# speedometer.net
KiCad netlist of a schematic drawn in EAGLE
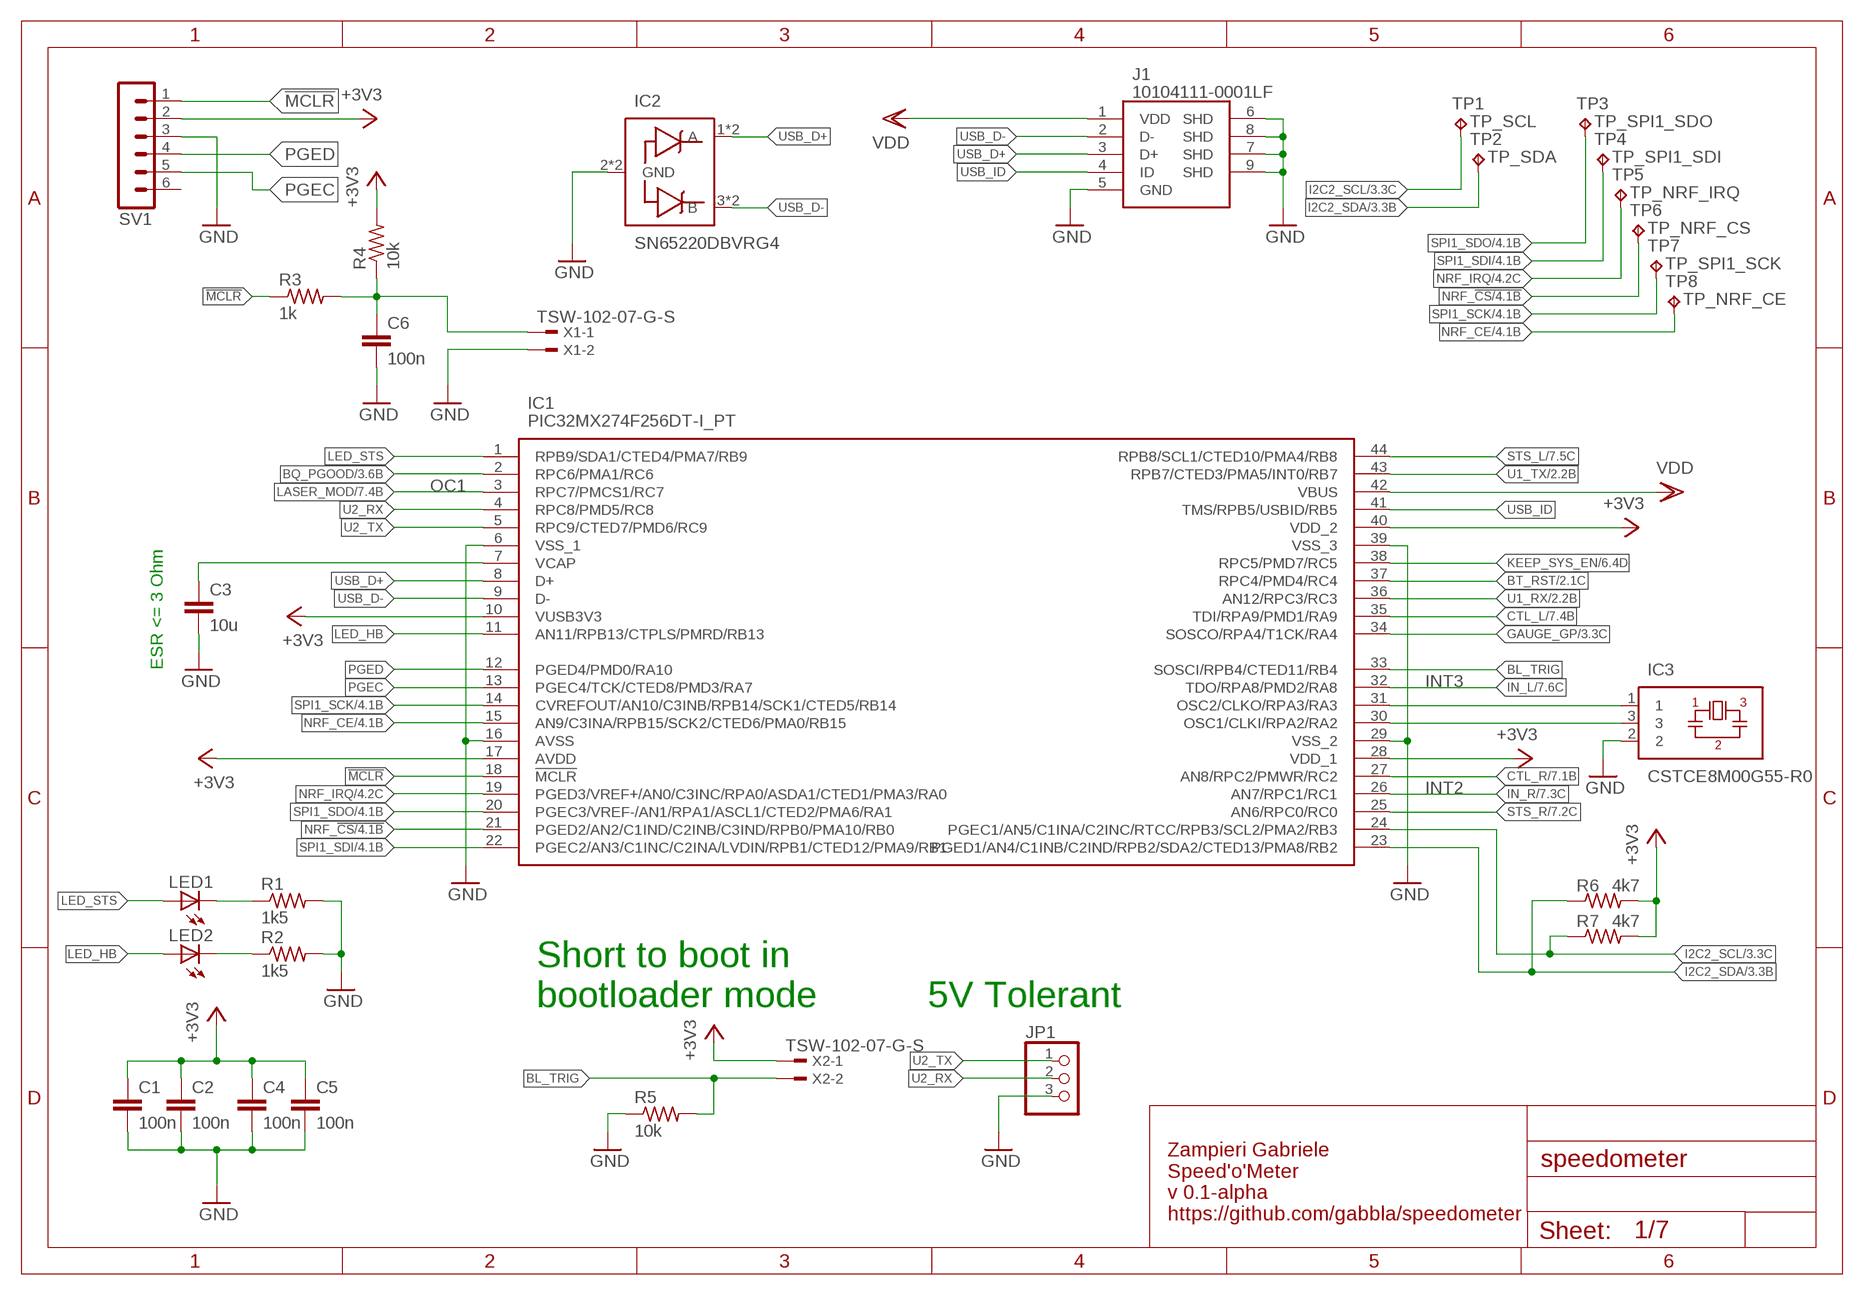
[diagram p0: schematic, sheet 1]
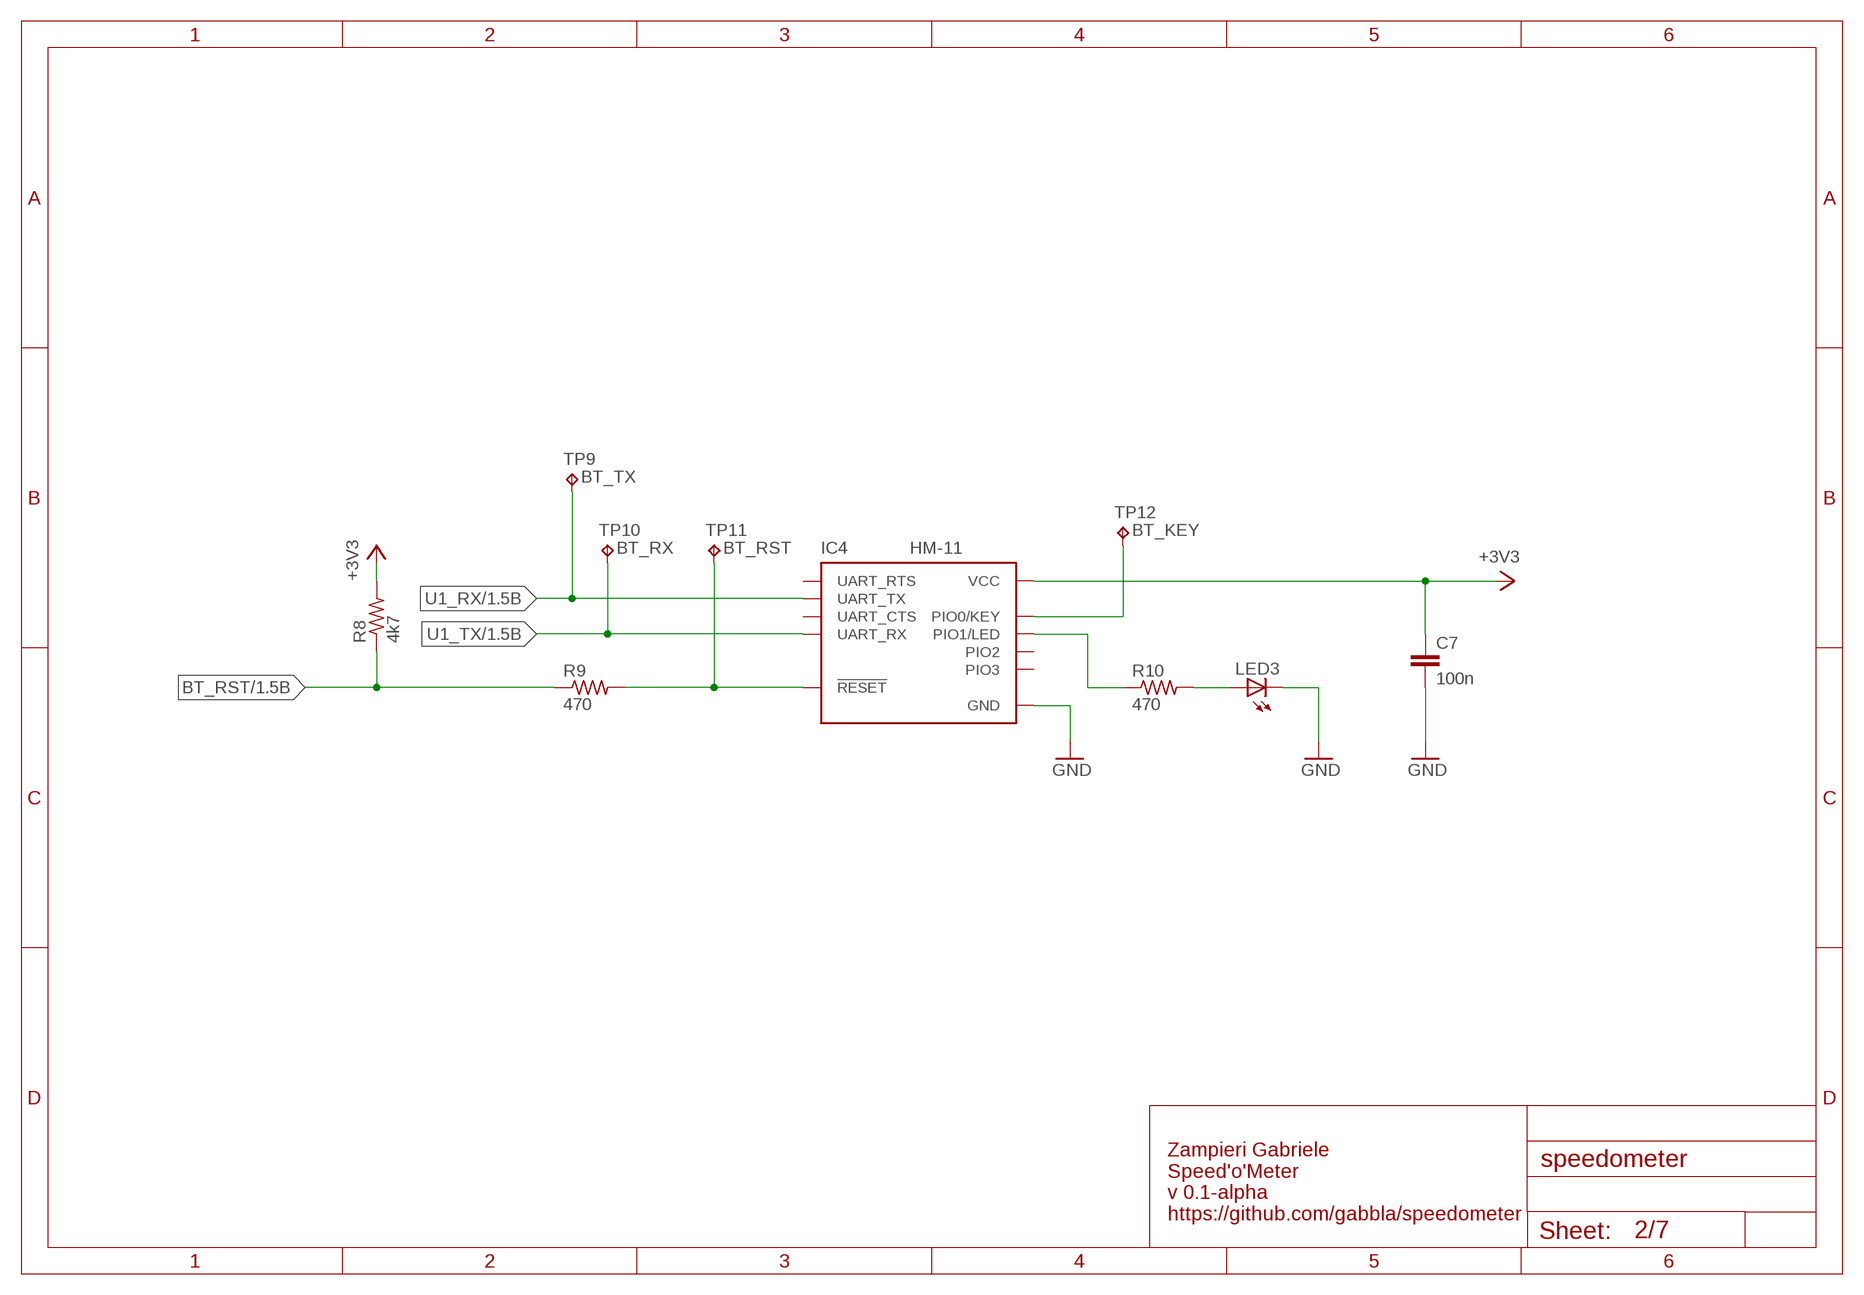
[diagram p1: schematic, sheet 2]
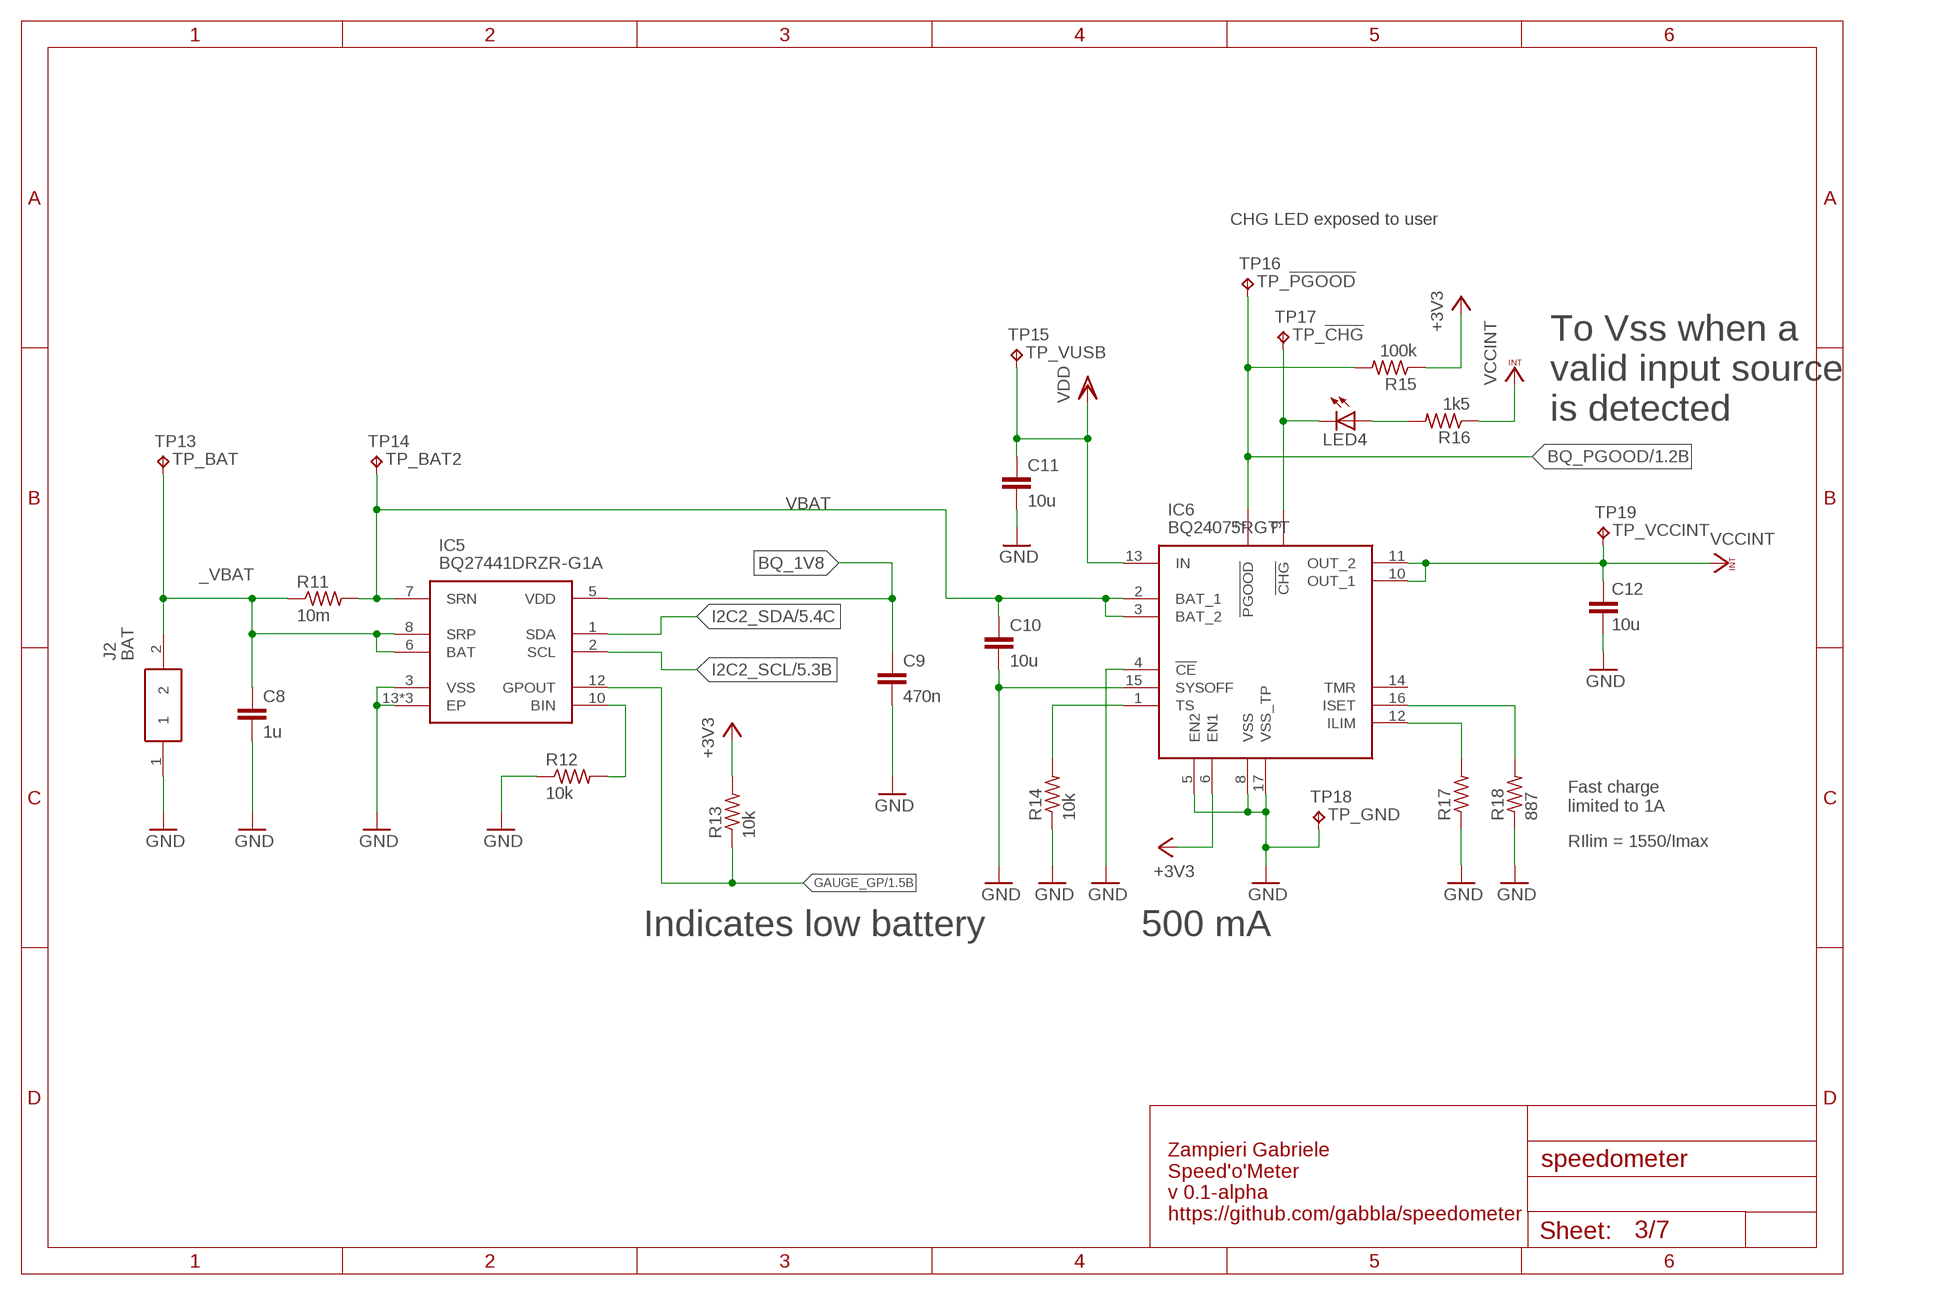
[diagram p2: schematic, sheet 3]
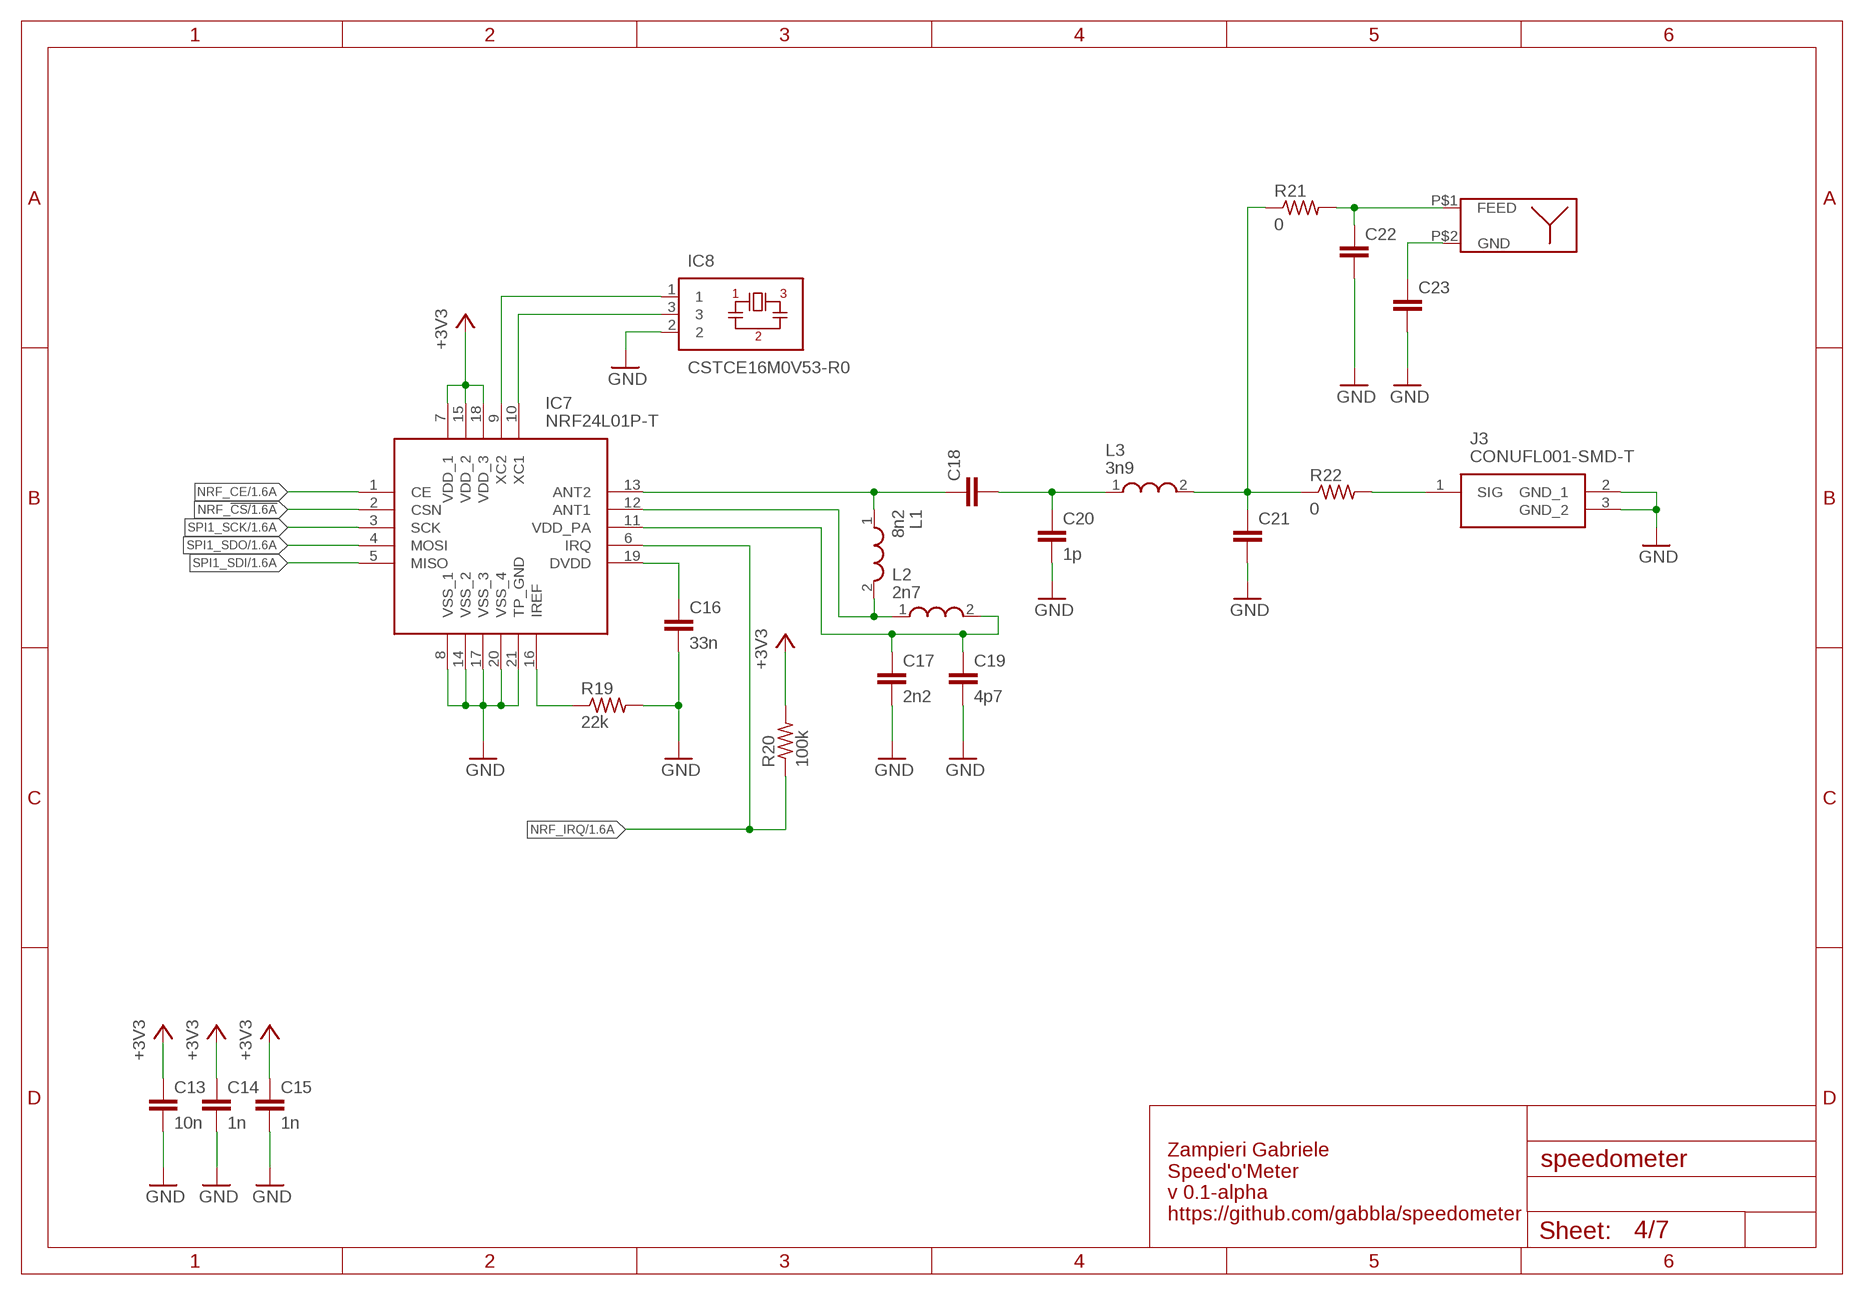
[diagram p3: schematic, sheet 4]
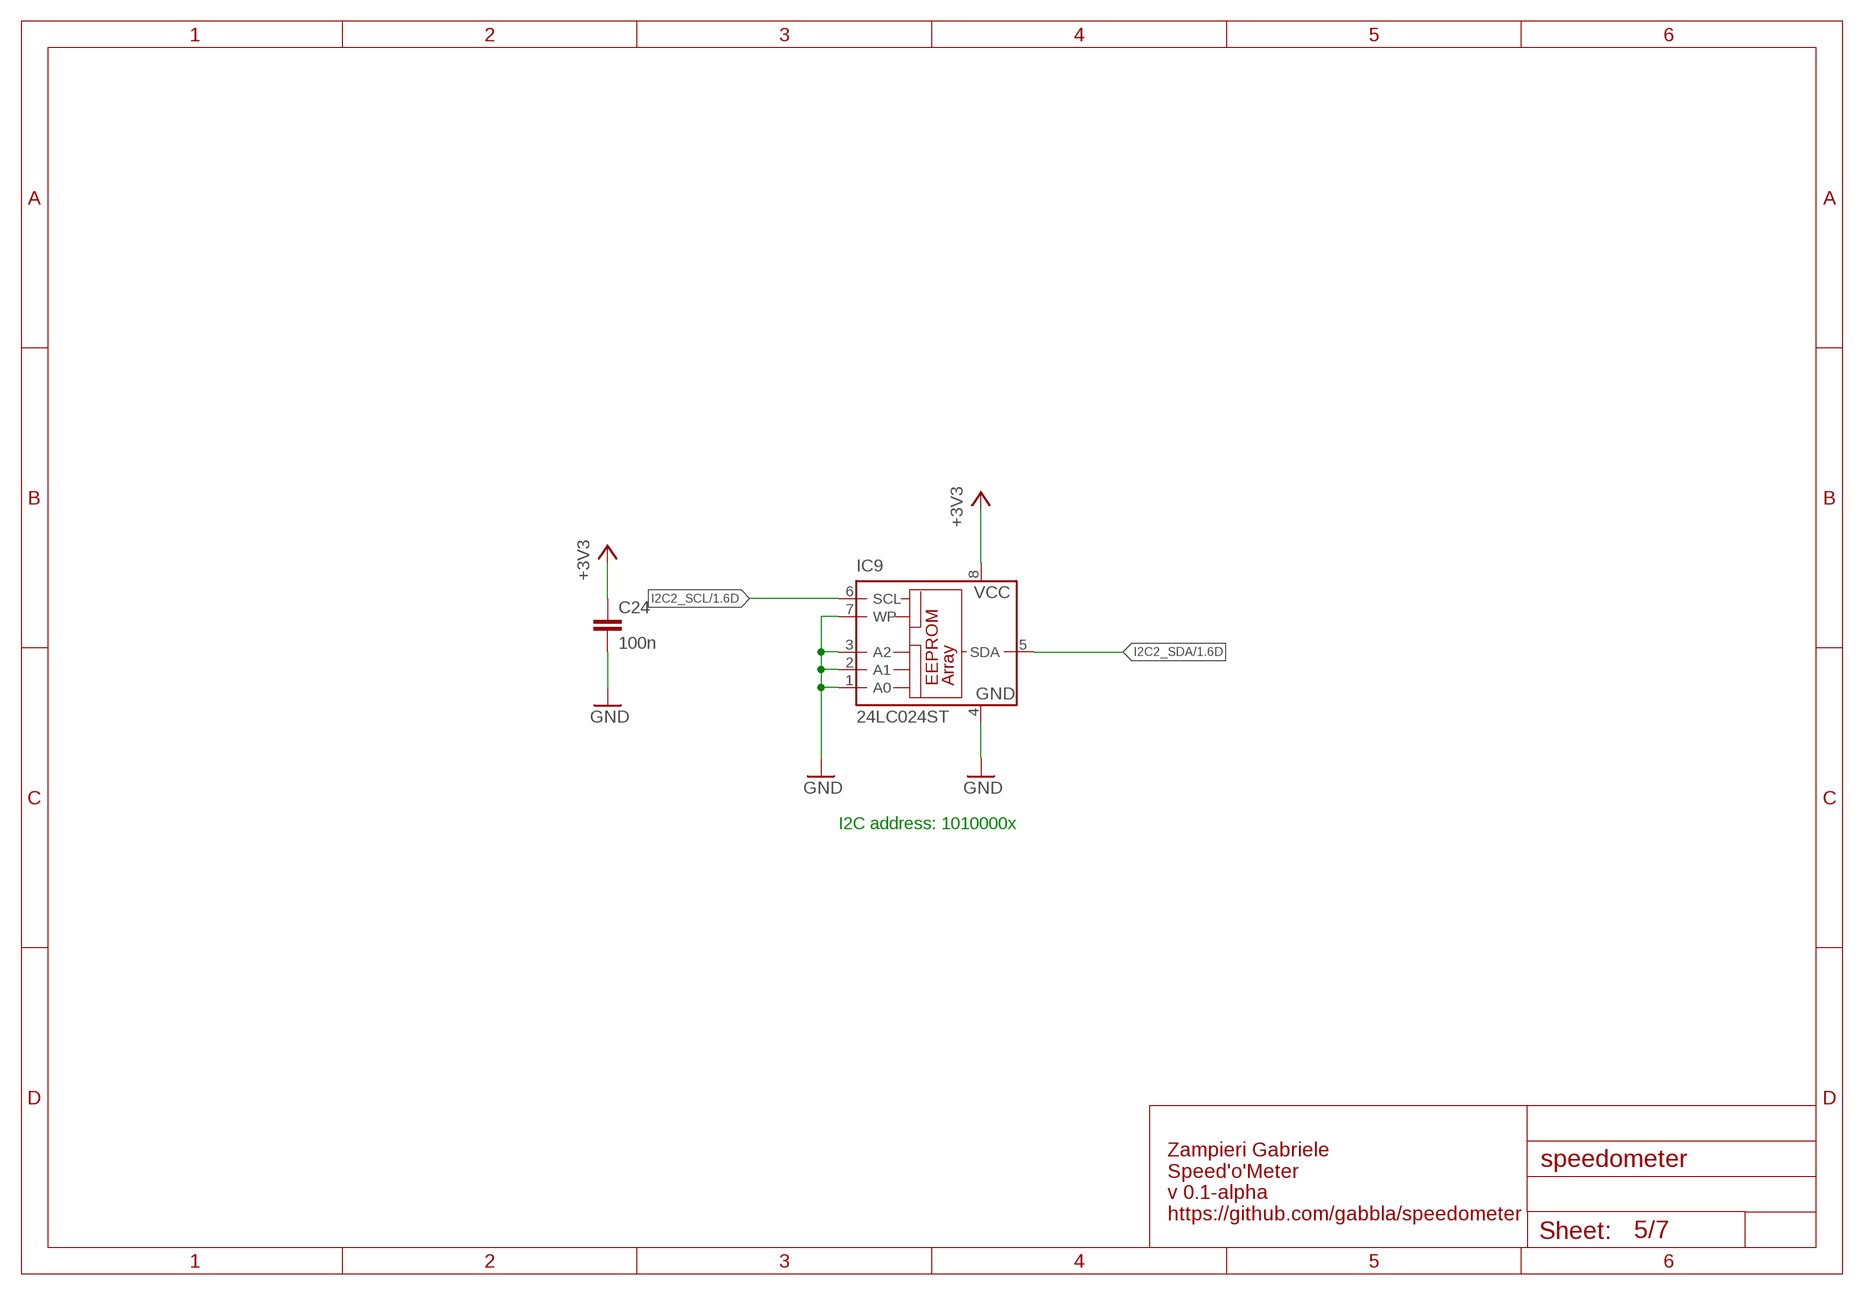
[diagram p4: schematic, sheet 5]
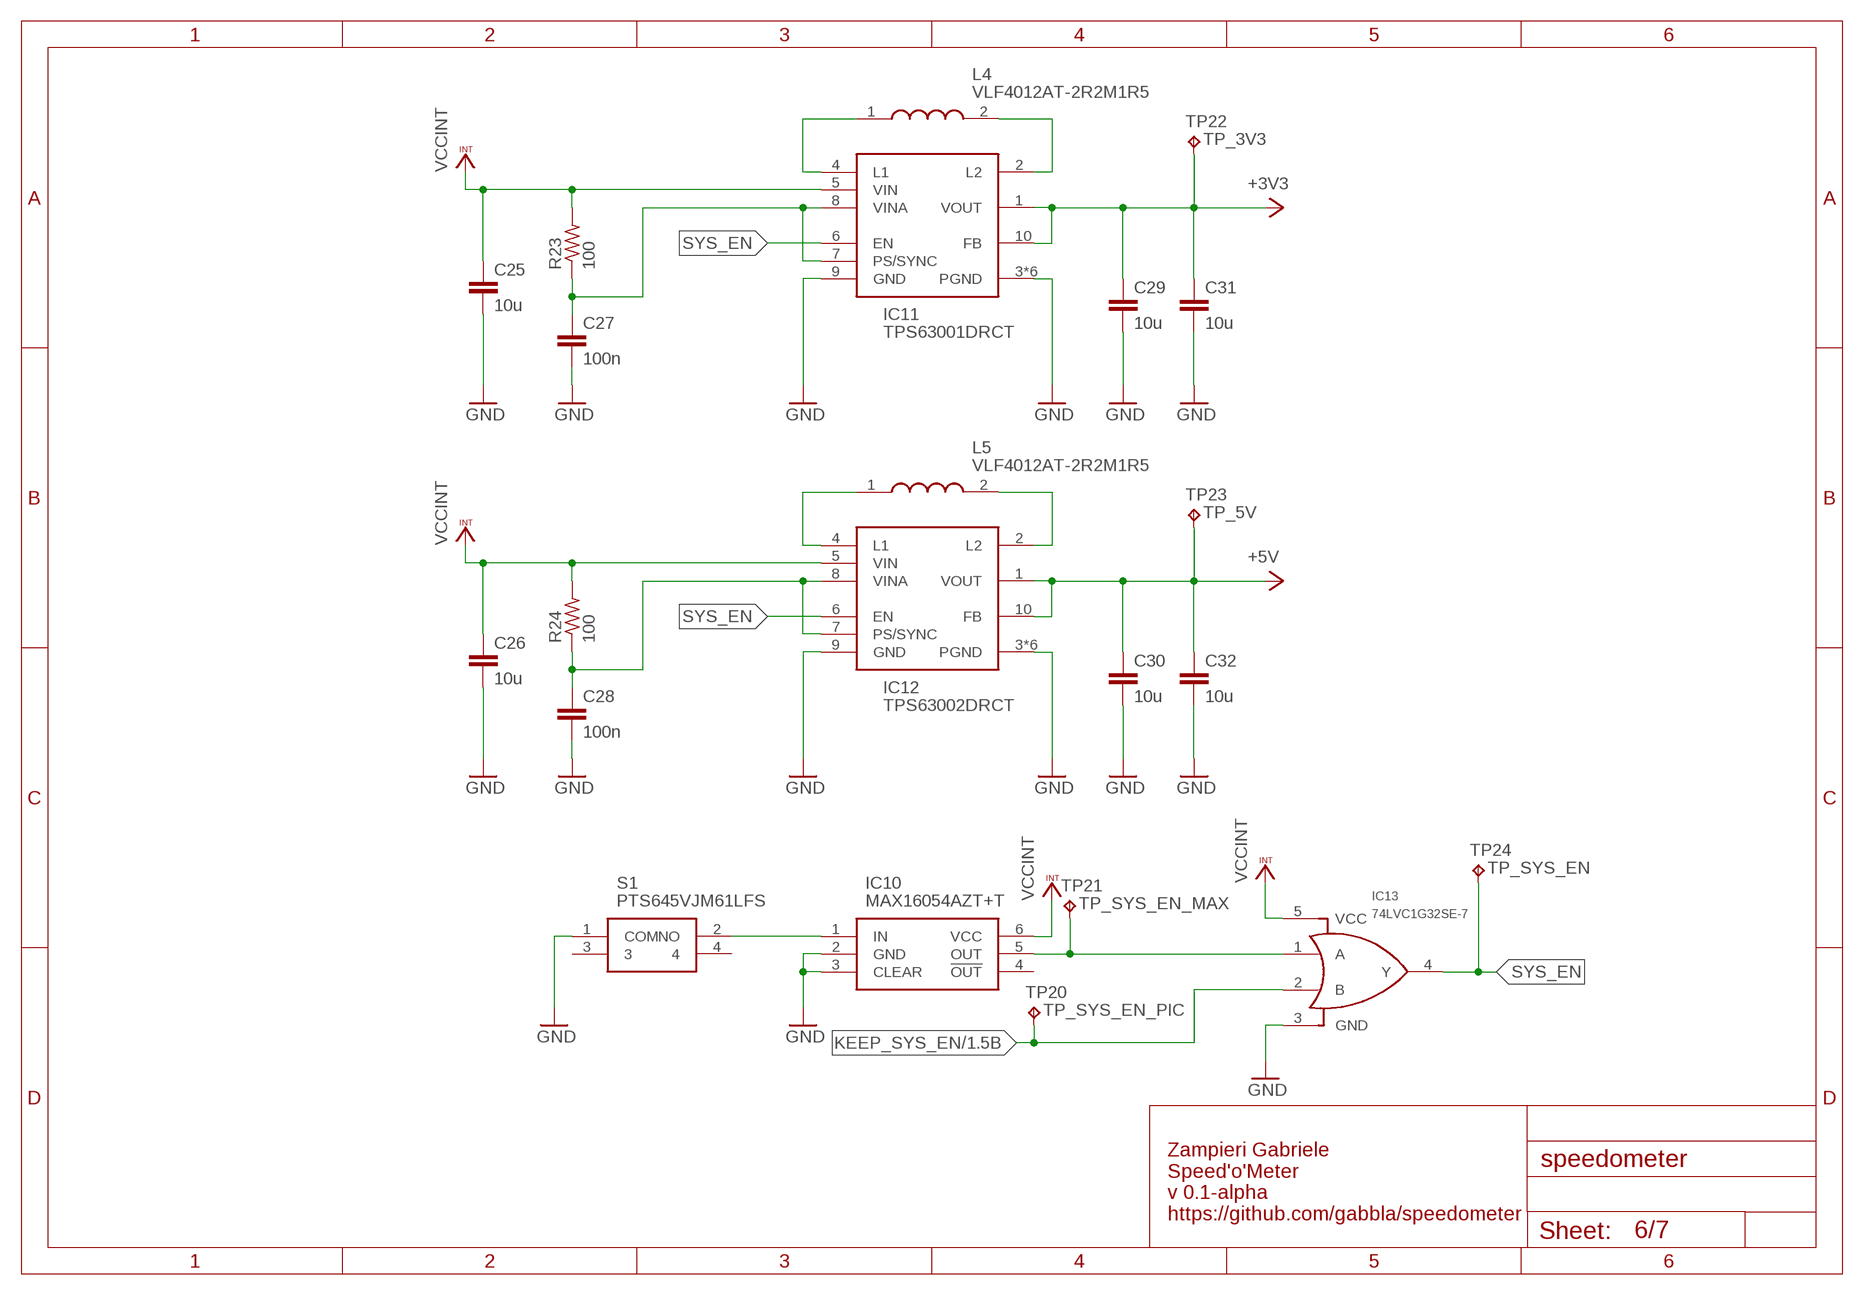
[diagram p5: schematic, sheet 6]
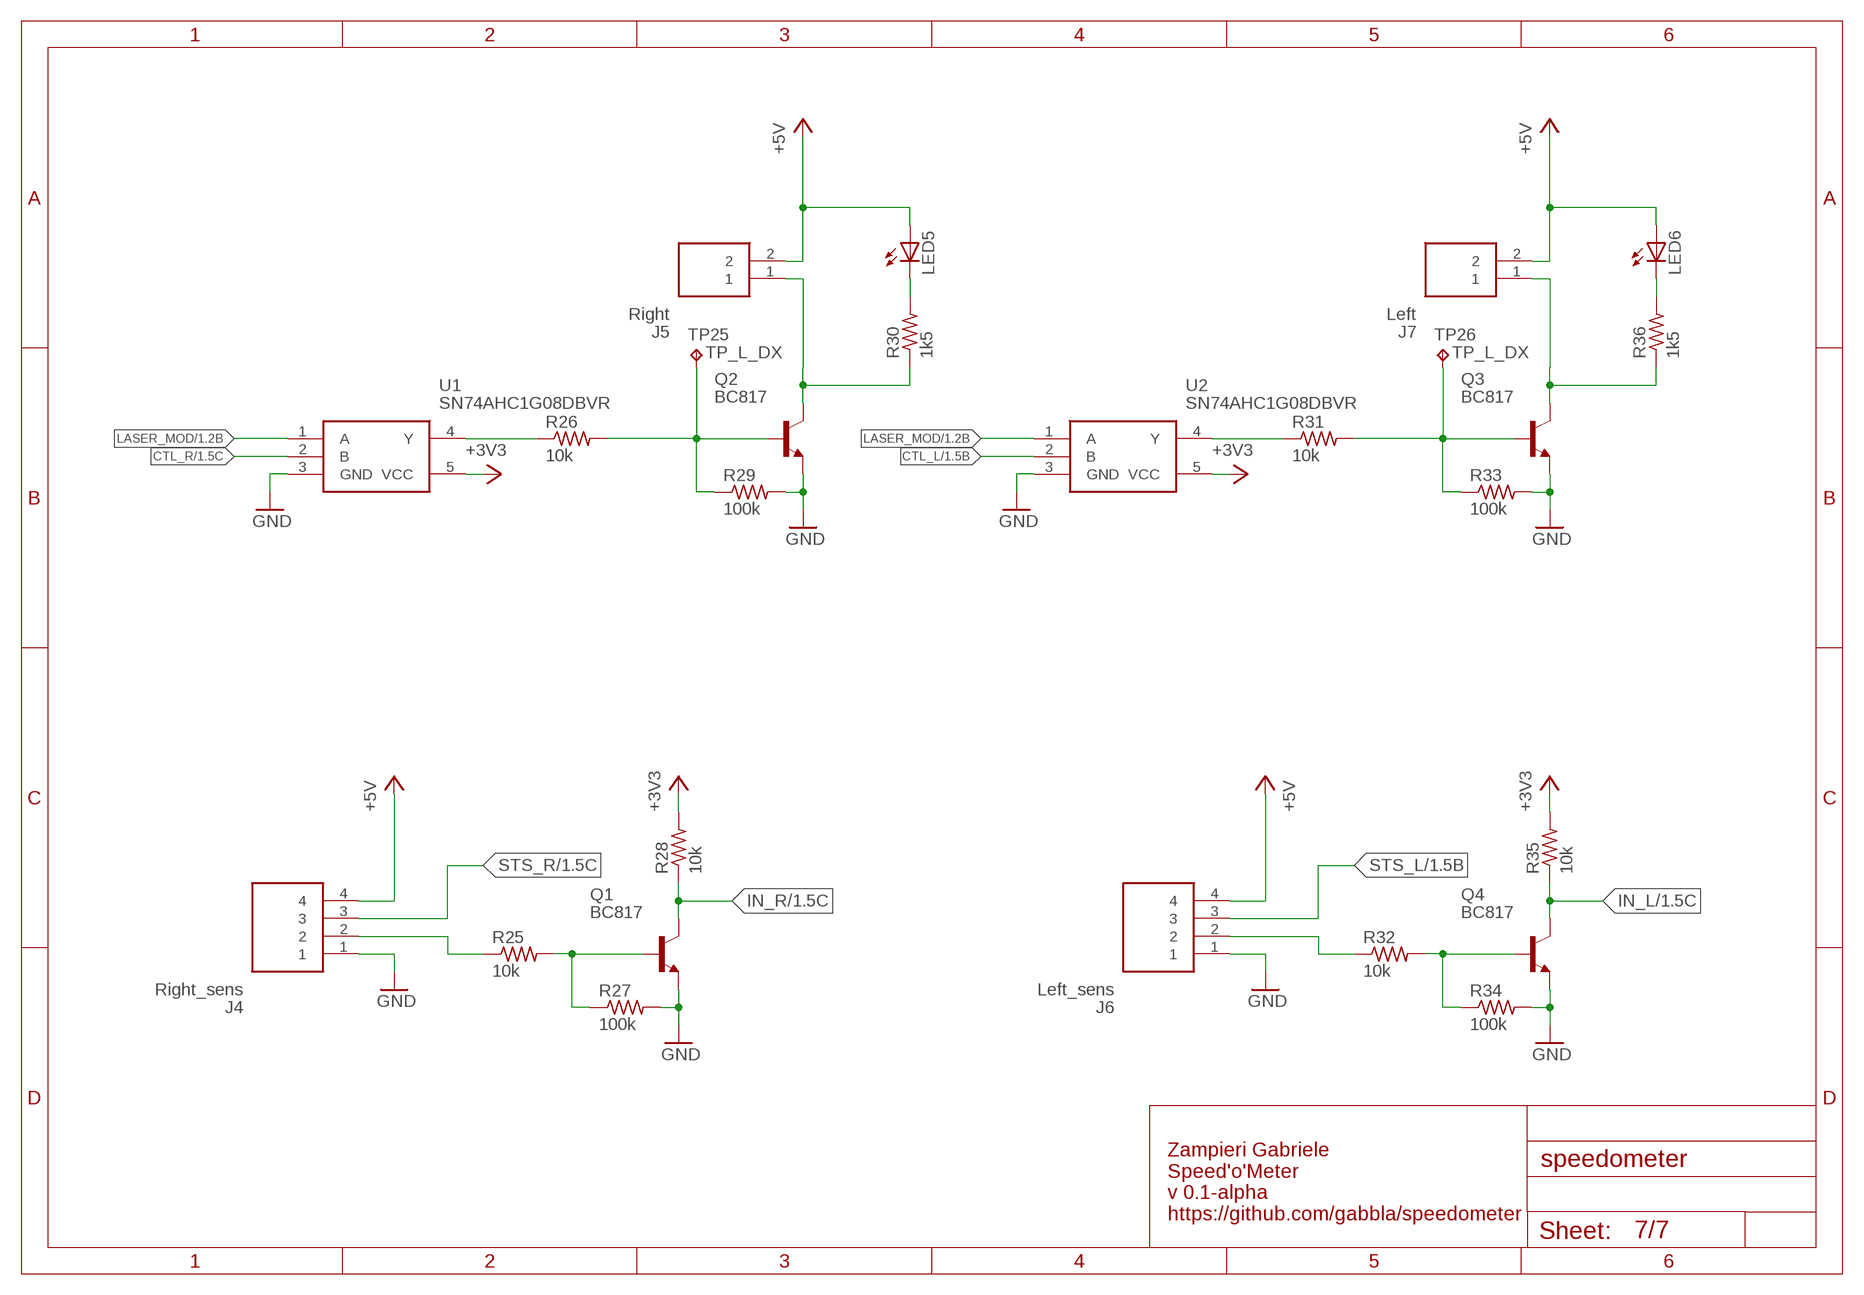
[diagram p6: schematic, sheet 7]

(export (version "E")
  (design (tool "Eeschema 10.0.6"))
  (components
    (comp (ref "C24")
      (value "100n")
      (footprint "eagle-import:C0603K")
      (libsource (lib "eagle-import") (part "C-EUC0603K"))
    )
    (comp (ref "IC9")
      (value "24LC024ST")
      (footprint "eagle-import:TSSOP8")
      (fields (field (name "MPN") "24LC024H-I/ST"))
      (libsource (lib "eagle-import") (part "24STLC024"))
    )
    (comp (ref "C1")
      (value "100n")
      (footprint "eagle-import:C0603K")
      (libsource (lib "eagle-import") (part "C-EUC0603K"))
    )
    (comp (ref "C2")
      (value "100n")
      (footprint "eagle-import:C0603K")
      (libsource (lib "eagle-import") (part "C-EUC0603K"))
    )
    (comp (ref "C3")
      (value "10u")
      (footprint "eagle-import:C0805K")
      (libsource (lib "eagle-import") (part "C-EUC0805K"))
    )
    (comp (ref "C4")
      (value "100n")
      (footprint "eagle-import:C0603K")
      (libsource (lib "eagle-import") (part "C-EUC0603K"))
    )
    (comp (ref "C5")
      (value "100n")
      (footprint "eagle-import:C0603K")
      (libsource (lib "eagle-import") (part "C-EUC0603K"))
    )
    (comp (ref "C6")
      (value "100n")
      (footprint "eagle-import:C0603K")
      (libsource (lib "eagle-import") (part "C-EUC0603K"))
    )
    (comp (ref "IC1")
      (value "PIC32MX274F256DT-I_PT")
      (footprint "eagle-import:QFP80P1200X1200X120-44N")
      (fields (field (name "ARROW_PART_NUMBER") "PIC32MX274F256DT-I/PT"))
      (libsource (lib "eagle-import") (part "PIC32MX274F256DT-I_PT"))
    )
    (comp (ref "IC2")
      (value "SN65220DBVRG4")
      (footprint "eagle-import:SOT95P280X145-6N")
      (libsource (lib "eagle-import") (part "SN65220DBVRG4"))
    )
    (comp (ref "IC3")
      (value "CSTCE8M00G55-R0")
      (footprint "eagle-import:CSTCE_G")
      (fields
        (field (name "ARROW_PART_NUMBER") "CSTCE12M0G15L99-R0")
        (field (name "RS_PART_NUMBER") "7926527P")
      )
      (libsource (lib "eagle-import") (part "CSTCE12M0G15L99-R0"))
    )
    (comp (ref "J1")
      (value "10104111-0001LF")
      (footprint "eagle-import:MICRO_USB_A_B_TYPE_RECEPTACLE")
      (fields (field (name "RS_PART_NUMBER") "1622014"))
      (libsource (lib "eagle-import") (part "10104111-0001LF"))
    )
    (comp (ref "JP1")
      (value "PINHD-1X3")
      (footprint "eagle-import:1X03")
      (libsource (lib "eagle-import") (part "PINHD-1X3"))
    )
    (comp (ref "LED1")
      (value "LED3MM")
      (footprint "eagle-import:LED3MM")
      (libsource (lib "eagle-import") (part "LED3MM"))
    )
    (comp (ref "LED2")
      (value "LEDCHIPLED_0805")
      (footprint "eagle-import:CHIPLED_0805")
      (libsource (lib "eagle-import") (part "LEDCHIPLED_0805"))
    )
    (comp (ref "R1")
      (value "1k5")
      (footprint "eagle-import:R0603")
      (libsource (lib "eagle-import") (part "R-US_R0603"))
    )
    (comp (ref "R2")
      (value "1k5")
      (footprint "eagle-import:R0603")
      (libsource (lib "eagle-import") (part "R-US_R0603"))
    )
    (comp (ref "R3")
      (value "1k")
      (footprint "eagle-import:R0603")
      (libsource (lib "eagle-import") (part "R-US_R0603"))
    )
    (comp (ref "R4")
      (value "10k")
      (footprint "eagle-import:R0603")
      (libsource (lib "eagle-import") (part "R-US_R0603"))
    )
    (comp (ref "R5")
      (value "10k")
      (footprint "eagle-import:R0603")
      (libsource (lib "eagle-import") (part "R-US_R0603"))
    )
    (comp (ref "R6")
      (value "4k7")
      (footprint "eagle-import:R0603")
      (libsource (lib "eagle-import") (part "R-US_R0603"))
    )
    (comp (ref "R7")
      (value "4k7")
      (footprint "eagle-import:R0603")
      (libsource (lib "eagle-import") (part "R-US_R0603"))
    )
    (comp (ref "SV1")
      (value "MA06-1")
      (footprint "eagle-import:MA06-1")
      (libsource (lib "eagle-import") (part "MA06-1"))
    )
    (comp (ref "TP1")
      (value "TPB1,27")
      (footprint "eagle-import:B1,27")
      (fields (field (name "TP_SIGNAL_NAME") "TP_SCL"))
      (libsource (lib "eagle-import") (part "TPB1,27"))
    )
    (comp (ref "TP2")
      (value "TPB1,27")
      (footprint "eagle-import:B1,27")
      (fields (field (name "TP_SIGNAL_NAME") "TP_SDA"))
      (libsource (lib "eagle-import") (part "TPB1,27"))
    )
    (comp (ref "TP3")
      (value "TPB1,27")
      (footprint "eagle-import:B1,27")
      (fields (field (name "TP_SIGNAL_NAME") "TP_SPI1_SDO"))
      (libsource (lib "eagle-import") (part "TPB1,27"))
    )
    (comp (ref "TP4")
      (value "TPB1,27")
      (footprint "eagle-import:B1,27")
      (fields (field (name "TP_SIGNAL_NAME") "TP_SPI1_SDI"))
      (libsource (lib "eagle-import") (part "TPB1,27"))
    )
    (comp (ref "TP5")
      (value "TPB1,27")
      (footprint "eagle-import:B1,27")
      (fields (field (name "TP_SIGNAL_NAME") "TP_NRF_IRQ"))
      (libsource (lib "eagle-import") (part "TPB1,27"))
    )
    (comp (ref "TP6")
      (value "TPB1,27")
      (footprint "eagle-import:B1,27")
      (fields (field (name "TP_SIGNAL_NAME") "TP_NRF_CS"))
      (libsource (lib "eagle-import") (part "TPB1,27"))
    )
    (comp (ref "TP7")
      (value "TPB1,27")
      (footprint "eagle-import:B1,27")
      (fields (field (name "TP_SIGNAL_NAME") "TP_SPI1_SCK"))
      (libsource (lib "eagle-import") (part "TPB1,27"))
    )
    (comp (ref "TP8")
      (value "TPB1,27")
      (footprint "eagle-import:B1,27")
      (fields (field (name "TP_SIGNAL_NAME") "TP_NRF_CE"))
      (libsource (lib "eagle-import") (part "TPB1,27"))
    )
    (comp (ref "X1")
      (value "TSW-102-07-G-S")
      (footprint "eagle-import:TSW-102-XX-G-S")
      (fields (field (name "MF") "Samtec Inc."))
      (libsource (lib "eagle-import") (part "TSW-102--G-S07"))
    )
    (comp (ref "X2")
      (value "TSW-102-07-G-S")
      (footprint "eagle-import:TSW-102-XX-G-S")
      (fields (field (name "MF") "Samtec Inc."))
      (libsource (lib "eagle-import") (part "TSW-102--G-S07"))
    )
    (comp (ref "C25")
      (value "10u")
      (footprint "eagle-import:C0805K")
      (libsource (lib "eagle-import") (part "C-EUC0805K"))
    )
    (comp (ref "C26")
      (value "10u")
      (footprint "eagle-import:C0805K")
      (libsource (lib "eagle-import") (part "C-EUC0805K"))
    )
    (comp (ref "C27")
      (value "100n")
      (footprint "eagle-import:C0603K")
      (libsource (lib "eagle-import") (part "C-EUC0603K"))
    )
    (comp (ref "C28")
      (value "100n")
      (footprint "eagle-import:C0603K")
      (libsource (lib "eagle-import") (part "C-EUC0603K"))
    )
    (comp (ref "C29")
      (value "10u")
      (footprint "eagle-import:C0805K")
      (libsource (lib "eagle-import") (part "C-EUC0805K"))
    )
    (comp (ref "C30")
      (value "10u")
      (footprint "eagle-import:C0805K")
      (libsource (lib "eagle-import") (part "C-EUC0805K"))
    )
    (comp (ref "C31")
      (value "10u")
      (footprint "eagle-import:C0805K")
      (libsource (lib "eagle-import") (part "C-EUC0805K"))
    )
    (comp (ref "C32")
      (value "10u")
      (footprint "eagle-import:C0805K")
      (libsource (lib "eagle-import") (part "C-EUC0805K"))
    )
    (comp (ref "IC10")
      (value "MAX16054AZT+T")
      (footprint "eagle-import:SOT95P275X110-6N")
      (fields (field (name "RS_PART_NUMBER") "9237416"))
      (libsource (lib "eagle-import") (part "MAX16054AZT+T"))
    )
    (comp (ref "IC11")
      (value "TPS63001DRCT")
      (footprint "eagle-import:SON50P300X300X100-11N")
      (fields (field (name "ARROW_PART_NUMBER") "TPS63000DRCT") (field (name "RS_PART_NUMBER") "0389334P"))
      (libsource (lib "eagle-import") (part "TPS63000DRCT"))
    )
    (comp (ref "IC12")
      (value "TPS63002DRCT")
      (footprint "eagle-import:SON50P300X300X100-11N")
      (fields (field (name "ARROW_PART_NUMBER") "TPS63000DRCT") (field (name "RS_PART_NUMBER") "0389334P"))
      (libsource (lib "eagle-import") (part "TPS63000DRCT"))
    )
    (comp (ref "IC13")
      (value "74LVC1G32SE-7")
      (footprint "eagle-import:SOT353")
      (libsource (lib "eagle-import") (part "74LVC1G32SE-7"))
    )
    (comp (ref "L4")
      (value "VLF4012AT-2R2M1R5")
      (footprint "eagle-import:LPS3015")
      (fields (field (name "ARROW_PART_NUMBER") "LPS3015-222MRB") (field (name "RS_PART_NUMBER") " 644-1952"))
      (libsource (lib "eagle-import") (part "LPS3015-222MRB"))
    )
    (comp (ref "L5")
      (value "VLF4012AT-2R2M1R5")
      (footprint "eagle-import:LPS3015")
      (fields (field (name "ARROW_PART_NUMBER") "LPS3015-222MRB") (field (name "RS_PART_NUMBER") " 644-1952"))
      (libsource (lib "eagle-import") (part "LPS3015-222MRB"))
    )
    (comp (ref "R23")
      (value "100")
      (footprint "eagle-import:R0603")
      (fields (field (name "RS_PART_NUMBER") "740-8978"))
      (libsource (lib "eagle-import") (part "R-US_R0603"))
    )
    (comp (ref "R24")
      (value "100")
      (footprint "eagle-import:R0603")
      (fields (field (name "RS_PART_NUMBER") "740-8978"))
      (libsource (lib "eagle-import") (part "R-US_R0603"))
    )
    (comp (ref "S1")
      (value "PTS645VJM61LFS")
      (footprint "eagle-import:PTS645VJM61LFS")
      (libsource (lib "eagle-import") (part "PTS645VJM61LFS"))
    )
    (comp (ref "TP20")
      (value "TPB1,27")
      (footprint "eagle-import:B1,27")
      (fields (field (name "TP_SIGNAL_NAME") "TP_SYS_EN_PIC"))
      (libsource (lib "eagle-import") (part "TPB1,27"))
    )
    (comp (ref "TP21")
      (value "TPB1,27")
      (footprint "eagle-import:B1,27")
      (fields (field (name "TP_SIGNAL_NAME") "TP_SYS_EN_MAX"))
      (libsource (lib "eagle-import") (part "TPB1,27"))
    )
    (comp (ref "TP22")
      (value "TPB1,27")
      (footprint "eagle-import:B1,27")
      (fields (field (name "TP_SIGNAL_NAME") "TP_3V3"))
      (libsource (lib "eagle-import") (part "TPB1,27"))
    )
    (comp (ref "TP23")
      (value "TPB1,27")
      (footprint "eagle-import:B1,27")
      (fields (field (name "TP_SIGNAL_NAME") "TP_5V"))
      (libsource (lib "eagle-import") (part "TPB1,27"))
    )
    (comp (ref "TP24")
      (value "TPB1,27")
      (footprint "eagle-import:B1,27")
      (fields (field (name "TP_SIGNAL_NAME") "TP_SYS_EN"))
      (libsource (lib "eagle-import") (part "TPB1,27"))
    )
    (comp (ref "C8")
      (value "1u")
      (footprint "eagle-import:C0603K")
      (libsource (lib "eagle-import") (part "C-EUC0603K"))
    )
    (comp (ref "C9")
      (value "470n")
      (footprint "eagle-import:C0603K")
      (libsource (lib "eagle-import") (part "C-EUC0603K"))
    )
    (comp (ref "C10")
      (value "10u")
      (footprint "eagle-import:C0805K")
      (libsource (lib "eagle-import") (part "C-EUC0805K"))
    )
    (comp (ref "C11")
      (value "10u")
      (footprint "eagle-import:C0805K")
      (libsource (lib "eagle-import") (part "C-EUC0805K"))
    )
    (comp (ref "C12")
      (value "10u")
      (footprint "eagle-import:C0805K")
      (libsource (lib "eagle-import") (part "C-EUC0805K"))
    )
    (comp (ref "IC5")
      (value "BQ27441DRZR-G1A")
      (footprint "eagle-import:BQ27441DRZRG1A")
      (libsource (lib "eagle-import") (part "BQ27441DRZR-G1A"))
    )
    (comp (ref "IC6")
      (value "BQ24075RGTT")
      (footprint "eagle-import:QFN50P300X300X80-17N")
      (fields (field (name "RS_PART_NUMBER") "8175815P"))
      (libsource (lib "eagle-import") (part "BQ24075RGTT"))
    )
    (comp (ref "J2")
      (value "BAT")
      (footprint "eagle-import:B2B-PH-SM4-TB")
      (fields
        (field (name "MANUFACTURER_PART_NUMBER") "B2B-PH-SM4-TB(LF)(SN)")
        (field (name "RS_PART_NUMBER") "6881325P")
      )
      (libsource (lib "eagle-import") (part "B2B-PH-SM4-TB(LF)(SN)"))
    )
    (comp (ref "LED4")
      (value "LED3MM")
      (footprint "eagle-import:LED3MM")
      (libsource (lib "eagle-import") (part "LED3MM"))
    )
    (comp (ref "R11")
      (value "10m")
      (footprint "eagle-import:R2512")
      (libsource (lib "eagle-import") (part "R-US_R2512"))
    )
    (comp (ref "R12")
      (value "10k")
      (footprint "eagle-import:R0603")
      (libsource (lib "eagle-import") (part "R-US_R0603"))
    )
    (comp (ref "R13")
      (value "10k")
      (footprint "eagle-import:R0603")
      (libsource (lib "eagle-import") (part "R-US_R0603"))
    )
    (comp (ref "R14")
      (value "10k")
      (footprint "eagle-import:R0603")
      (libsource (lib "eagle-import") (part "R-US_R0603"))
    )
    (comp (ref "R15")
      (value "100k")
      (footprint "eagle-import:R0603")
      (libsource (lib "eagle-import") (part "R-US_R0603"))
    )
    (comp (ref "R16")
      (value "1k5")
      (footprint "eagle-import:R0603")
      (libsource (lib "eagle-import") (part "R-US_R0603"))
    )
    (comp (ref "R17")
      (value "R-US_R0603")
      (footprint "eagle-import:R0603")
      (libsource (lib "eagle-import") (part "R-US_R0603"))
    )
    (comp (ref "R18")
      (value "887")
      (footprint "eagle-import:R0603")
      (libsource (lib "eagle-import") (part "R-US_R0603"))
    )
    (comp (ref "TP13")
      (value "TPB1,27")
      (footprint "eagle-import:B1,27")
      (fields (field (name "TP_SIGNAL_NAME") "TP_BAT"))
      (libsource (lib "eagle-import") (part "TPB1,27"))
    )
    (comp (ref "TP14")
      (value "TPB1,27")
      (footprint "eagle-import:B1,27")
      (fields (field (name "TP_SIGNAL_NAME") "TP_BAT2"))
      (libsource (lib "eagle-import") (part "TPB1,27"))
    )
    (comp (ref "TP15")
      (value "TPB1,27")
      (footprint "eagle-import:B1,27")
      (fields (field (name "TP_SIGNAL_NAME") "TP_VUSB"))
      (libsource (lib "eagle-import") (part "TPB1,27"))
    )
    (comp (ref "TP16")
      (value "TPB1,27")
      (footprint "eagle-import:B1,27")
      (fields (field (name "TP_SIGNAL_NAME") "TP_!PGOOD"))
      (libsource (lib "eagle-import") (part "TPB1,27"))
    )
    (comp (ref "TP17")
      (value "TPB1,27")
      (footprint "eagle-import:B1,27")
      (fields (field (name "TP_SIGNAL_NAME") "TP_!CHG"))
      (libsource (lib "eagle-import") (part "TPB1,27"))
    )
    (comp (ref "TP18")
      (value "TPB1,27")
      (footprint "eagle-import:B1,27")
      (fields (field (name "TP_SIGNAL_NAME") "TP_GND"))
      (libsource (lib "eagle-import") (part "TPB1,27"))
    )
    (comp (ref "TP19")
      (value "TPB1,27")
      (footprint "eagle-import:B1,27")
      (fields (field (name "TP_SIGNAL_NAME") "TP_VCCINT"))
      (libsource (lib "eagle-import") (part "TPB1,27"))
    )
    (comp (ref "C7")
      (value "100n")
      (footprint "eagle-import:C0603K")
      (libsource (lib "eagle-import") (part "C-EUC0603K"))
    )
    (comp (ref "IC4")
      (value "HM-11")
      (footprint "eagle-import:HM-11")
      (libsource (lib "eagle-import") (part "HM-11"))
    )
    (comp (ref "LED3")
      (value "LED3MM")
      (footprint "eagle-import:LED3MM")
      (libsource (lib "eagle-import") (part "LED3MM"))
    )
    (comp (ref "R8")
      (value "4k7")
      (footprint "eagle-import:R0603")
      (libsource (lib "eagle-import") (part "R-US_R0603"))
    )
    (comp (ref "R9")
      (value "470")
      (footprint "eagle-import:R0603")
      (libsource (lib "eagle-import") (part "R-US_R0603"))
    )
    (comp (ref "R10")
      (value "470")
      (footprint "eagle-import:R0603")
      (libsource (lib "eagle-import") (part "R-US_R0603"))
    )
    (comp (ref "TP9")
      (value "TPB1,27")
      (footprint "eagle-import:B1,27")
      (fields (field (name "TP_SIGNAL_NAME") "BT_TX"))
      (libsource (lib "eagle-import") (part "TPB1,27"))
    )
    (comp (ref "TP10")
      (value "TPB1,27")
      (footprint "eagle-import:B1,27")
      (fields (field (name "TP_SIGNAL_NAME") "BT_RX"))
      (libsource (lib "eagle-import") (part "TPB1,27"))
    )
    (comp (ref "TP11")
      (value "TPB1,27")
      (footprint "eagle-import:B1,27")
      (fields (field (name "TP_SIGNAL_NAME") "BT_RST"))
      (libsource (lib "eagle-import") (part "TPB1,27"))
    )
    (comp (ref "TP12")
      (value "TPB1,27")
      (footprint "eagle-import:B1,27")
      (fields (field (name "TP_SIGNAL_NAME") "BT_KEY"))
      (libsource (lib "eagle-import") (part "TPB1,27"))
    )
    (comp (ref "J4")
      (value "Right_sens")
      (footprint "eagle-import:SHDR4W64P0X250_1X4_1240X575X70")
      (fields (field (name "ARROW_PART_NUMBER") "B4B-XH-A(LF)(SN)") (field (name "RS_PART_NUMBER") "1724913"))
      (libsource (lib "eagle-import") (part "B4B-XH-A(LF)(SN)"))
    )
    (comp (ref "J5")
      (value "Right")
      (footprint "eagle-import:SHDR2W64P0X250_1X2_740X575X700")
      (fields (field (name "ARROW_PART_NUMBER") "B2B-XH-A(LF)(SN)") (field (name "RS_PART_NUMBER") "1667312"))
      (libsource (lib "eagle-import") (part "B2B-XH-A(LF)(SN)"))
    )
    (comp (ref "J6")
      (value "Left_sens")
      (footprint "eagle-import:SHDR4W64P0X250_1X4_1240X575X70")
      (fields
        (field (name "ARROW_PART_NUMBER") "B4B-XH-A(LF)(SN)")
        (field (name "RS_PART_NUMBER") "1724913")
        (field (name "SPICEPREFIX") "E")
      )
      (libsource (lib "eagle-import") (part "B4B-XH-A(LF)(SN)"))
    )
    (comp (ref "J7")
      (value "Left")
      (footprint "eagle-import:SHDR2W64P0X250_1X2_740X575X700")
      (fields (field (name "ARROW_PART_NUMBER") "B2B-XH-A(LF)(SN)") (field (name "RS_PART_NUMBER") "1667312"))
      (libsource (lib "eagle-import") (part "B2B-XH-A(LF)(SN)"))
    )
    (comp (ref "LED5")
      (value "LEDCHIPLED_1206")
      (footprint "eagle-import:CHIPLED_1206")
      (libsource (lib "eagle-import") (part "LEDCHIPLED_1206"))
    )
    (comp (ref "LED6")
      (value "LEDCHIPLED_1206")
      (footprint "eagle-import:CHIPLED_1206")
      (libsource (lib "eagle-import") (part "LEDCHIPLED_1206"))
    )
    (comp (ref "Q1")
      (value "BC817")
      (footprint "eagle-import:SOT23-BEC")
      (libsource (lib "eagle-import") (part "BC817SMD-16LT1"))
    )
    (comp (ref "Q2")
      (value "BC817")
      (footprint "eagle-import:SOT23-BEC")
      (libsource (lib "eagle-import") (part "BC817SMD-16LT1"))
    )
    (comp (ref "Q3")
      (value "BC817")
      (footprint "eagle-import:SOT23-BEC")
      (libsource (lib "eagle-import") (part "BC817SMD-16LT1"))
    )
    (comp (ref "Q4")
      (value "BC817")
      (footprint "eagle-import:SOT23-BEC")
      (fields (field (name "SPICEPREFIX") "Q"))
      (libsource (lib "eagle-import") (part "BC817SMD-16LT1"))
    )
    (comp (ref "R25")
      (value "10k")
      (footprint "eagle-import:R0603")
      (libsource (lib "eagle-import") (part "R-US_R0603"))
    )
    (comp (ref "R26")
      (value "10k")
      (footprint "eagle-import:R0603")
      (libsource (lib "eagle-import") (part "R-US_R0603"))
    )
    (comp (ref "R27")
      (value "100k")
      (footprint "eagle-import:R0603")
      (libsource (lib "eagle-import") (part "R-US_R0603"))
    )
    (comp (ref "R28")
      (value "10k")
      (footprint "eagle-import:R0603")
      (libsource (lib "eagle-import") (part "R-US_R0603"))
    )
    (comp (ref "R29")
      (value "100k")
      (footprint "eagle-import:R0603")
      (libsource (lib "eagle-import") (part "R-US_R0603"))
    )
    (comp (ref "R30")
      (value "1k5")
      (footprint "eagle-import:R0603")
      (libsource (lib "eagle-import") (part "R-US_R0603"))
    )
    (comp (ref "R31")
      (value "10k")
      (footprint "eagle-import:R0603")
      (libsource (lib "eagle-import") (part "R-US_R0603"))
    )
    (comp (ref "R32")
      (value "10k")
      (footprint "eagle-import:R0603")
      (libsource (lib "eagle-import") (part "R-US_R0603"))
    )
    (comp (ref "R33")
      (value "100k")
      (footprint "eagle-import:R0603")
      (libsource (lib "eagle-import") (part "R-US_R0603"))
    )
    (comp (ref "R34")
      (value "100k")
      (footprint "eagle-import:R0603")
      (libsource (lib "eagle-import") (part "R-US_R0603"))
    )
    (comp (ref "R35")
      (value "10k")
      (footprint "eagle-import:R0603")
      (libsource (lib "eagle-import") (part "R-US_R0603"))
    )
    (comp (ref "R36")
      (value "1k5")
      (footprint "eagle-import:R0603")
      (libsource (lib "eagle-import") (part "R-US_R0603"))
    )
    (comp (ref "TP25")
      (value "TPB1,27")
      (footprint "eagle-import:B1,27")
      (fields (field (name "TP_SIGNAL_NAME") "TP_L_DX"))
      (libsource (lib "eagle-import") (part "TPB1,27"))
    )
    (comp (ref "TP26")
      (value "TPB1,27")
      (footprint "eagle-import:B1,27")
      (fields (field (name "TP_SIGNAL_NAME") "TP_L_DX"))
      (libsource (lib "eagle-import") (part "TPB1,27"))
    )
    (comp (ref "U1")
      (value "SN74AHC1G08DBVR")
      (footprint "eagle-import:SOT95P280X145-5N")
      (fields (field (name "RS_PART_NUMBER") "1218343"))
      (libsource (lib "eagle-import") (part "SN74AHC1G08DBVR"))
    )
    (comp (ref "U2")
      (value "SN74AHC1G08DBVR")
      (footprint "eagle-import:SOT95P280X145-5N")
      (fields (field (name "RS_PART_NUMBER") "1218343"))
      (libsource (lib "eagle-import") (part "SN74AHC1G08DBVR"))
    )
    (comp (ref "ANT1")
      (value "M310210")
      (footprint "eagle-import:M310210")
      (libsource (lib "eagle-import") (part "M310210"))
    )
    (comp (ref "C13")
      (value "10n")
      (footprint "eagle-import:C0603K")
      (libsource (lib "eagle-import") (part "C-EUC0603K"))
    )
    (comp (ref "C14")
      (value "1n")
      (footprint "eagle-import:C0603K")
      (libsource (lib "eagle-import") (part "C-EUC0603K"))
    )
    (comp (ref "C15")
      (value "1n")
      (footprint "eagle-import:C0603K")
      (libsource (lib "eagle-import") (part "C-EUC0603K"))
    )
    (comp (ref "C16")
      (value "33n")
      (footprint "eagle-import:C0402K")
      (libsource (lib "eagle-import") (part "C-EUC0402K"))
    )
    (comp (ref "C17")
      (value "2n2")
      (footprint "eagle-import:C0402K")
      (libsource (lib "eagle-import") (part "C-EUC0402K"))
    )
    (comp (ref "C18")
      (value "C-EUC0402K")
      (footprint "eagle-import:C0402K")
      (libsource (lib "eagle-import") (part "C-EUC0402K"))
    )
    (comp (ref "C19")
      (value "4p7")
      (footprint "eagle-import:C0402K")
      (libsource (lib "eagle-import") (part "C-EUC0402K"))
    )
    (comp (ref "C20")
      (value "1p")
      (footprint "eagle-import:C0402K")
      (libsource (lib "eagle-import") (part "C-EUC0402K"))
    )
    (comp (ref "C21")
      (value "C-EUC0402K")
      (footprint "eagle-import:C0402K")
      (libsource (lib "eagle-import") (part "C-EUC0402K"))
    )
    (comp (ref "C22")
      (value "C-EUC0402K")
      (footprint "eagle-import:C0402K")
      (libsource (lib "eagle-import") (part "C-EUC0402K"))
    )
    (comp (ref "C23")
      (value "C-EUC0402K")
      (footprint "eagle-import:C0402K")
      (libsource (lib "eagle-import") (part "C-EUC0402K"))
    )
    (comp (ref "IC7")
      (value "NRF24L01P-T")
      (footprint "eagle-import:QFN50P400X400X95-21N")
      (fields (field (name "ARROW_PART_NUMBER") "nRF24L01P-T") (field (name "RS_PART_NUMBER") "8855748P"))
      (libsource (lib "eagle-import") (part "NRF24L01P-T"))
    )
    (comp (ref "IC8")
      (value "CSTCE16M0V53-R0")
      (footprint "eagle-import:CSTCE_G")
      (fields
        (field (name "ARROW_PART_NUMBER") "CSTCE12M0G15L99-R0")
        (field (name "RS_PART_NUMBER") "7926527P")
      )
      (libsource (lib "eagle-import") (part "CSTCE12M0G15L99-R0"))
    )
    (comp (ref "J3")
      (value "CONUFL001-SMD-T")
      (footprint "eagle-import:CONUFL001-SMD")
      (libsource (lib "eagle-import") (part "CONUFL001-SMD-T"))
    )
    (comp (ref "L1")
      (value "8n2")
      (footprint "eagle-import:C0402K")
      (libsource (lib "eagle-import") (part "INDUCTOR"))
    )
    (comp (ref "L2")
      (value "2n7")
      (footprint "eagle-import:C0402K")
      (libsource (lib "eagle-import") (part "INDUCTOR"))
    )
    (comp (ref "L3")
      (value "3n9")
      (footprint "eagle-import:C0402K")
      (libsource (lib "eagle-import") (part "INDUCTOR"))
    )
    (comp (ref "R19")
      (value "22k")
      (footprint "eagle-import:R0603")
      (libsource (lib "eagle-import") (part "R-US_R0603"))
    )
    (comp (ref "R20")
      (value "100k")
      (footprint "eagle-import:R0603")
      (libsource (lib "eagle-import") (part "R-US_R0603"))
    )
    (comp (ref "R21")
      (value "0")
      (footprint "eagle-import:R0402")
      (libsource (lib "eagle-import") (part "R-US_R0402"))
    )
    (comp (ref "R22")
      (value "0")
      (footprint "eagle-import:R0402")
      (libsource (lib "eagle-import") (part "R-US_R0402"))
    )
  )
  (nets
    (net (code "1") (name "+3V3") (class "Default")
      (node (ref "C1") (pin "1") (pinfunction "1_1") (pintype "passive"))
      (node (ref "C13") (pin "1") (pinfunction "1_1") (pintype "passive"))
      (node (ref "C14") (pin "1") (pinfunction "1_1") (pintype "passive"))
      (node (ref "C15") (pin "1") (pinfunction "1_1") (pintype "passive"))
      (node (ref "C2") (pin "1") (pinfunction "1_1") (pintype "passive"))
      (node (ref "C24") (pin "1") (pinfunction "1_1") (pintype "passive"))
      (node (ref "C29") (pin "1") (pinfunction "1_1") (pintype "passive"))
      (node (ref "C31") (pin "1") (pinfunction "1_1") (pintype "passive"))
      (node (ref "C4") (pin "1") (pinfunction "1_1") (pintype "passive"))
      (node (ref "C5") (pin "1") (pinfunction "1_1") (pintype "passive"))
      (node (ref "C7") (pin "1") (pinfunction "1_1") (pintype "passive"))
      (node (ref "IC1") (pin "10") (pinfunction "VUSB3V3_10") (pintype "bidirectional"))
      (node (ref "IC1") (pin "17") (pinfunction "AVDD_17") (pintype "bidirectional"))
      (node (ref "IC1") (pin "28") (pinfunction "VDD_1_28") (pintype "bidirectional"))
      (node (ref "IC1") (pin "40") (pinfunction "VDD_2_40") (pintype "bidirectional"))
      (node (ref "IC11") (pin "1") (pinfunction "VOUT_1") (pintype "output"))
      (node (ref "IC11") (pin "10") (pinfunction "FB_10") (pintype "bidirectional"))
      (node (ref "IC4") (pin "VCC") (pinfunction "VCC_VCC") (pintype "bidirectional"))
      (node (ref "IC6") (pin "6") (pinfunction "EN1_6") (pintype "bidirectional"))
      (node (ref "IC7") (pin "15") (pinfunction "VDD_2_15") (pintype "bidirectional"))
      (node (ref "IC7") (pin "18") (pinfunction "VDD_3_18") (pintype "bidirectional"))
      (node (ref "IC7") (pin "7") (pinfunction "VDD_1_7") (pintype "bidirectional"))
      (node (ref "IC9") (pin "8") (pinfunction "VCC_8") (pintype "power_in"))
      (node (ref "R13") (pin "2") (pinfunction "2_2") (pintype "passive"))
      (node (ref "R15") (pin "1") (pinfunction "1_1") (pintype "passive"))
      (node (ref "R20") (pin "2") (pinfunction "2_2") (pintype "passive"))
      (node (ref "R28") (pin "2") (pinfunction "2_2") (pintype "passive"))
      (node (ref "R35") (pin "2") (pinfunction "2_2") (pintype "passive"))
      (node (ref "R4") (pin "2") (pinfunction "2_2") (pintype "passive"))
      (node (ref "R6") (pin "2") (pinfunction "2_2") (pintype "passive"))
      (node (ref "R7") (pin "2") (pinfunction "2_2") (pintype "passive"))
      (node (ref "R8") (pin "2") (pinfunction "2_2") (pintype "passive"))
      (node (ref "SV1") (pin "2") (pinfunction "2_2") (pintype "passive"))
      (node (ref "TP22") (pin "TP") (pinfunction "TP_TP") (pintype "input"))
      (node (ref "U1") (pin "5") (pinfunction "VCC_5") (pintype "bidirectional"))
      (node (ref "U2") (pin "5") (pinfunction "VCC_5") (pintype "bidirectional"))
      (node (ref "X2") (pin "1") (pinfunction "1_1") (pintype "passive"))
    )
    (net (code "2") (name "+5V") (class "Default")
      (node (ref "C30") (pin "1") (pinfunction "1_1") (pintype "passive"))
      (node (ref "C32") (pin "1") (pinfunction "1_1") (pintype "passive"))
      (node (ref "IC12") (pin "1") (pinfunction "VOUT_1") (pintype "output"))
      (node (ref "IC12") (pin "10") (pinfunction "FB_10") (pintype "bidirectional"))
      (node (ref "J4") (pin "4") (pinfunction "4_4") (pintype "bidirectional"))
      (node (ref "J5") (pin "2") (pinfunction "2_2") (pintype "bidirectional"))
      (node (ref "J6") (pin "4") (pinfunction "4_4") (pintype "bidirectional"))
      (node (ref "J7") (pin "2") (pinfunction "2_2") (pintype "bidirectional"))
      (node (ref "LED5") (pin "A") (pinfunction "A_A") (pintype "passive"))
      (node (ref "LED6") (pin "A") (pinfunction "A_A") (pintype "passive"))
      (node (ref "TP23") (pin "TP") (pinfunction "TP_TP") (pintype "input"))
    )
    (net (code "3") (name "BL_TRIG") (class "Default")
      (node (ref "IC1") (pin "33") (pinfunction "SOSCI/RPB4/CTED11/RB4_33") (pintype "bidirectional"))
      (node (ref "R5") (pin "2") (pinfunction "2_2") (pintype "passive"))
      (node (ref "X2") (pin "2") (pinfunction "1_2") (pintype "passive"))
    )
    (net (code "4") (name "BQ_1V8") (class "Default")
      (node (ref "C9") (pin "1") (pinfunction "1_1") (pintype "passive"))
      (node (ref "IC5") (pin "5") (pinfunction "VDD_5") (pintype "bidirectional"))
    )
    (net (code "5") (name "BQ_PGOOD") (class "Default")
      (node (ref "IC1") (pin "2") (pinfunction "RPC6/PMA1/RC6_2") (pintype "bidirectional"))
      (node (ref "IC6") (pin "7") (pinfunction "~{PGOOD}_7") (pintype "bidirectional"))
      (node (ref "R15") (pin "2") (pinfunction "2_2") (pintype "passive"))
      (node (ref "TP16") (pin "TP") (pinfunction "TP_TP") (pintype "input"))
    )
    (net (code "6") (name "BT_RST") (class "Default")
      (node (ref "IC1") (pin "37") (pinfunction "RPC4/PMD4/RC4_37") (pintype "bidirectional"))
      (node (ref "R8") (pin "1") (pinfunction "1_1") (pintype "passive"))
      (node (ref "R9") (pin "1") (pinfunction "1_1") (pintype "passive"))
    )
    (net (code "7") (name "CTL_L") (class "Default")
      (node (ref "IC1") (pin "35") (pinfunction "TDI/RPA9/PMD1/RA9_35") (pintype "bidirectional"))
      (node (ref "U2") (pin "2") (pinfunction "B_2") (pintype "bidirectional"))
    )
    (net (code "8") (name "CTL_R") (class "Default")
      (node (ref "IC1") (pin "27") (pinfunction "AN8/RPC2/PMWR/RC2_27") (pintype "bidirectional"))
      (node (ref "U1") (pin "2") (pinfunction "B_2") (pintype "bidirectional"))
    )
    (net (code "9") (name "GAUGE_GP") (class "Default")
      (node (ref "IC1") (pin "34") (pinfunction "SOSCO/RPA4/T1CK/RA4_34") (pintype "bidirectional"))
      (node (ref "IC5") (pin "12") (pinfunction "GPOUT_12") (pintype "bidirectional"))
      (node (ref "R13") (pin "1") (pinfunction "1_1") (pintype "passive"))
    )
    (net (code "10") (name "GND") (class "Default")
      (node (ref "C1") (pin "2") (pinfunction "2_2") (pintype "passive"))
      (node (ref "C10") (pin "2") (pinfunction "2_2") (pintype "passive"))
      (node (ref "C11") (pin "2") (pinfunction "2_2") (pintype "passive"))
      (node (ref "C12") (pin "2") (pinfunction "2_2") (pintype "passive"))
      (node (ref "C13") (pin "2") (pinfunction "2_2") (pintype "passive"))
      (node (ref "C14") (pin "2") (pinfunction "2_2") (pintype "passive"))
      (node (ref "C15") (pin "2") (pinfunction "2_2") (pintype "passive"))
      (node (ref "C16") (pin "2") (pinfunction "2_2") (pintype "passive"))
      (node (ref "C17") (pin "2") (pinfunction "2_2") (pintype "passive"))
      (node (ref "C19") (pin "2") (pinfunction "2_2") (pintype "passive"))
      (node (ref "C2") (pin "2") (pinfunction "2_2") (pintype "passive"))
      (node (ref "C20") (pin "2") (pinfunction "2_2") (pintype "passive"))
      (node (ref "C21") (pin "2") (pinfunction "2_2") (pintype "passive"))
      (node (ref "C22") (pin "2") (pinfunction "2_2") (pintype "passive"))
      (node (ref "C23") (pin "2") (pinfunction "2_2") (pintype "passive"))
      (node (ref "C24") (pin "2") (pinfunction "2_2") (pintype "passive"))
      (node (ref "C25") (pin "2") (pinfunction "2_2") (pintype "passive"))
      (node (ref "C26") (pin "2") (pinfunction "2_2") (pintype "passive"))
      (node (ref "C27") (pin "2") (pinfunction "2_2") (pintype "passive"))
      (node (ref "C28") (pin "2") (pinfunction "2_2") (pintype "passive"))
      (node (ref "C29") (pin "2") (pinfunction "2_2") (pintype "passive"))
      (node (ref "C3") (pin "2") (pinfunction "2_2") (pintype "passive"))
      (node (ref "C30") (pin "2") (pinfunction "2_2") (pintype "passive"))
      (node (ref "C31") (pin "2") (pinfunction "2_2") (pintype "passive"))
      (node (ref "C32") (pin "2") (pinfunction "2_2") (pintype "passive"))
      (node (ref "C4") (pin "2") (pinfunction "2_2") (pintype "passive"))
      (node (ref "C5") (pin "2") (pinfunction "2_2") (pintype "passive"))
      (node (ref "C6") (pin "2") (pinfunction "2_2") (pintype "passive"))
      (node (ref "C7") (pin "2") (pinfunction "2_2") (pintype "passive"))
      (node (ref "C8") (pin "2") (pinfunction "2_2") (pintype "passive"))
      (node (ref "C9") (pin "2") (pinfunction "2_2") (pintype "passive"))
      (node (ref "IC1") (pin "16") (pinfunction "AVSS_16") (pintype "bidirectional"))
      (node (ref "IC1") (pin "29") (pinfunction "VSS_2_29") (pintype "bidirectional"))
      (node (ref "IC1") (pin "39") (pinfunction "VSS_3_39") (pintype "bidirectional"))
      (node (ref "IC1") (pin "6") (pinfunction "VSS_1_6") (pintype "bidirectional"))
      (node (ref "IC10") (pin "2") (pinfunction "GND_2") (pintype "power_in"))
      (node (ref "IC10") (pin "3") (pinfunction "CLEAR_3") (pintype "bidirectional"))
      (node (ref "IC11") (pin "11") (pinfunction "PGND_11") (pintype "power_in"))
      (node (ref "IC11") (pin "3") (pinfunction "PGND_3") (pintype "power_in"))
      (node (ref "IC11") (pin "9") (pinfunction "GND_9") (pintype "power_in"))
      (node (ref "IC11") (pin "EP1") (pinfunction "PGND_EP1") (pintype "power_in"))
      (node (ref "IC11") (pin "EP2") (pinfunction "PGND_EP2") (pintype "power_in"))
      (node (ref "IC11") (pin "EP3") (pinfunction "PGND_EP3") (pintype "power_in"))
      (node (ref "IC11") (pin "EP4") (pinfunction "PGND_EP4") (pintype "power_in"))
      (node (ref "IC12") (pin "11") (pinfunction "PGND_11") (pintype "power_in"))
      (node (ref "IC12") (pin "3") (pinfunction "PGND_3") (pintype "power_in"))
      (node (ref "IC12") (pin "9") (pinfunction "GND_9") (pintype "power_in"))
      (node (ref "IC12") (pin "EP1") (pinfunction "PGND_EP1") (pintype "power_in"))
      (node (ref "IC12") (pin "EP2") (pinfunction "PGND_EP2") (pintype "power_in"))
      (node (ref "IC12") (pin "EP3") (pinfunction "PGND_EP3") (pintype "power_in"))
      (node (ref "IC12") (pin "EP4") (pinfunction "PGND_EP4") (pintype "power_in"))
      (node (ref "IC13") (pin "3") (pinfunction "GND_3") (pintype "bidirectional"))
      (node (ref "IC2") (pin "2") (pinfunction "GND_2") (pintype "power_in"))
      (node (ref "IC2") (pin "5") (pinfunction "GND_5") (pintype "power_in"))
      (node (ref "IC3") (pin "2") (pinfunction "2_2") (pintype "bidirectional"))
      (node (ref "IC4") (pin "GND") (pinfunction "GND_GND") (pintype "bidirectional"))
      (node (ref "IC5") (pin "13") (pinfunction "EP_13") (pintype "bidirectional"))
      (node (ref "IC5") (pin "14") (pinfunction "EP_14") (pintype "bidirectional"))
      (node (ref "IC5") (pin "15") (pinfunction "EP_15") (pintype "bidirectional"))
      (node (ref "IC5") (pin "3") (pinfunction "VSS_3") (pintype "bidirectional"))
      (node (ref "IC6") (pin "15") (pinfunction "SYSOFF_15") (pintype "bidirectional"))
      (node (ref "IC6") (pin "17") (pinfunction "VSS_TP_17") (pintype "power_in"))
      (node (ref "IC6") (pin "4") (pinfunction "~{CE}_4") (pintype "bidirectional"))
      (node (ref "IC6") (pin "5") (pinfunction "EN2_5") (pintype "bidirectional"))
      (node (ref "IC6") (pin "8") (pinfunction "VSS_8") (pintype "power_in"))
      (node (ref "IC7") (pin "14") (pinfunction "VSS_2_14") (pintype "bidirectional"))
      (node (ref "IC7") (pin "17") (pinfunction "VSS_3_17") (pintype "bidirectional"))
      (node (ref "IC7") (pin "20") (pinfunction "VSS_4_20") (pintype "bidirectional"))
      (node (ref "IC7") (pin "21") (pinfunction "TP_GND_21") (pintype "bidirectional"))
      (node (ref "IC7") (pin "8") (pinfunction "VSS_1_8") (pintype "bidirectional"))
      (node (ref "IC8") (pin "2") (pinfunction "2_2") (pintype "bidirectional"))
      (node (ref "IC9") (pin "1") (pinfunction "A0_1") (pintype "input"))
      (node (ref "IC9") (pin "2") (pinfunction "A1_2") (pintype "input"))
      (node (ref "IC9") (pin "3") (pinfunction "A2_3") (pintype "input"))
      (node (ref "IC9") (pin "4") (pinfunction "GND_4") (pintype "power_in"))
      (node (ref "IC9") (pin "7") (pinfunction "WP_7") (pintype "input"))
      (node (ref "J1") (pin "5") (pinfunction "GND_5") (pintype "bidirectional"))
      (node (ref "J1") (pin "6") (pinfunction "SHD_6") (pintype "bidirectional"))
      (node (ref "J1") (pin "7") (pinfunction "SHD_7") (pintype "bidirectional"))
      (node (ref "J1") (pin "8") (pinfunction "SHD_8") (pintype "bidirectional"))
      (node (ref "J1") (pin "9") (pinfunction "SHD_9") (pintype "bidirectional"))
      (node (ref "J2") (pin "1") (pinfunction "1_1") (pintype "bidirectional"))
      (node (ref "J3") (pin "2") (pinfunction "GND_1_2") (pintype "bidirectional"))
      (node (ref "J3") (pin "3") (pinfunction "GND_2_3") (pintype "bidirectional"))
      (node (ref "J4") (pin "1") (pinfunction "1_1") (pintype "bidirectional"))
      (node (ref "J6") (pin "1") (pinfunction "1_1") (pintype "bidirectional"))
      (node (ref "JP1") (pin "3") (pinfunction "3_3") (pintype "passive"))
      (node (ref "LED3") (pin "K") (pinfunction "C_K") (pintype "passive"))
      (node (ref "Q1") (pin "E") (pinfunction "E_E") (pintype "passive"))
      (node (ref "Q2") (pin "E") (pinfunction "E_E") (pintype "passive"))
      (node (ref "Q3") (pin "E") (pinfunction "E_E") (pintype "passive"))
      (node (ref "Q4") (pin "E") (pinfunction "E_E") (pintype "passive"))
      (node (ref "R1") (pin "2") (pinfunction "2_2") (pintype "passive"))
      (node (ref "R12") (pin "1") (pinfunction "1_1") (pintype "passive"))
      (node (ref "R14") (pin "1") (pinfunction "1_1") (pintype "passive"))
      (node (ref "R17") (pin "1") (pinfunction "1_1") (pintype "passive"))
      (node (ref "R18") (pin "1") (pinfunction "1_1") (pintype "passive"))
      (node (ref "R19") (pin "2") (pinfunction "2_2") (pintype "passive"))
      (node (ref "R2") (pin "2") (pinfunction "2_2") (pintype "passive"))
      (node (ref "R27") (pin "2") (pinfunction "2_2") (pintype "passive"))
      (node (ref "R29") (pin "2") (pinfunction "2_2") (pintype "passive"))
      (node (ref "R33") (pin "2") (pinfunction "2_2") (pintype "passive"))
      (node (ref "R34") (pin "2") (pinfunction "2_2") (pintype "passive"))
      (node (ref "R5") (pin "1") (pinfunction "1_1") (pintype "passive"))
      (node (ref "S1") (pin "1") (pinfunction "COM_1") (pintype "bidirectional"))
      (node (ref "SV1") (pin "3") (pinfunction "3_3") (pintype "passive"))
      (node (ref "TP18") (pin "TP") (pinfunction "TP_TP") (pintype "input"))
      (node (ref "U1") (pin "3") (pinfunction "GND_3") (pintype "bidirectional"))
      (node (ref "U2") (pin "3") (pinfunction "GND_3") (pintype "bidirectional"))
      (node (ref "X1") (pin "2") (pinfunction "1_2") (pintype "passive"))
    )
    (net (code "11") (name "I2C2_SCL") (class "Default")
      (node (ref "IC1") (pin "24") (pinfunction "PGEC1/AN5/C1INA/C2INC/RTCC/RPB3/SCL2/PMA2/RB3_24") (pintype "bidirectional"))
      (node (ref "IC5") (pin "2") (pinfunction "SCL_2") (pintype "bidirectional"))
      (node (ref "IC9") (pin "6") (pinfunction "SCL_6") (pintype "input"))
      (node (ref "R7") (pin "1") (pinfunction "1_1") (pintype "passive"))
      (node (ref "TP1") (pin "TP") (pinfunction "TP_TP") (pintype "input"))
    )
    (net (code "12") (name "I2C2_SDA") (class "Default")
      (node (ref "IC1") (pin "23") (pinfunction "PGED1/AN4/C1INB/C2IND/RPB2/SDA2/CTED13/PMA8/RB2_23") (pintype "bidirectional"))
      (node (ref "IC5") (pin "1") (pinfunction "SDA_1") (pintype "bidirectional"))
      (node (ref "IC9") (pin "5") (pinfunction "SDA_5") (pintype "bidirectional"))
      (node (ref "R6") (pin "1") (pinfunction "1_1") (pintype "passive"))
      (node (ref "TP2") (pin "TP") (pinfunction "TP_TP") (pintype "input"))
    )
    (net (code "13") (name "IN_L") (class "Default")
      (node (ref "IC1") (pin "32") (pinfunction "TDO/RPA8/PMD2/RA8_32") (pintype "bidirectional"))
      (node (ref "Q4") (pin "C") (pinfunction "C_C") (pintype "passive"))
      (node (ref "R35") (pin "1") (pinfunction "1_1") (pintype "passive"))
    )
    (net (code "14") (name "IN_R") (class "Default")
      (node (ref "IC1") (pin "26") (pinfunction "AN7/RPC1/RC1_26") (pintype "bidirectional"))
      (node (ref "Q1") (pin "C") (pinfunction "C_C") (pintype "passive"))
      (node (ref "R28") (pin "1") (pinfunction "1_1") (pintype "passive"))
    )
    (net (code "15") (name "KEEP_SYS_EN") (class "Default")
      (node (ref "IC1") (pin "38") (pinfunction "RPC5/PMD7/RC5_38") (pintype "bidirectional"))
      (node (ref "IC13") (pin "2") (pinfunction "B_2") (pintype "bidirectional"))
      (node (ref "TP20") (pin "TP") (pinfunction "TP_TP") (pintype "input"))
    )
    (net (code "16") (name "LASER_MOD") (class "Default")
      (node (ref "IC1") (pin "3") (pinfunction "RPC7/PMCS1/RC7_3") (pintype "bidirectional"))
      (node (ref "U1") (pin "1") (pinfunction "A_1") (pintype "bidirectional"))
      (node (ref "U2") (pin "1") (pinfunction "A_1") (pintype "bidirectional"))
    )
    (net (code "17") (name "LED_HB") (class "Default")
      (node (ref "IC1") (pin "11") (pinfunction "AN11/RPB13/CTPLS/PMRD/RB13_11") (pintype "bidirectional"))
      (node (ref "LED2") (pin "A") (pinfunction "A_A") (pintype "passive"))
    )
    (net (code "18") (name "LED_STS") (class "Default")
      (node (ref "IC1") (pin "1") (pinfunction "RPB9/SDA1/CTED4/PMA7/RB9_1") (pintype "bidirectional"))
      (node (ref "LED1") (pin "A") (pinfunction "A_A") (pintype "passive"))
    )
    (net (code "19") (name "NRF_CE") (class "Default")
      (node (ref "IC1") (pin "15") (pinfunction "AN9/C3INA/RPB15/SCK2/CTED6/PMA0/RB15_15") (pintype "bidirectional"))
      (node (ref "IC7") (pin "1") (pinfunction "CE_1") (pintype "bidirectional"))
      (node (ref "TP8") (pin "TP") (pinfunction "TP_TP") (pintype "input"))
    )
    (net (code "20") (name "NRF_IRQ") (class "Default")
      (node (ref "IC1") (pin "19") (pinfunction "PGED3/VREF+/AN0/C3INC/RPA0/ASDA1/CTED1/PMA3/RA0_19") (pintype "bidirectional"))
      (node (ref "IC7") (pin "6") (pinfunction "IRQ_6") (pintype "bidirectional"))
      (node (ref "R20") (pin "1") (pinfunction "1_1") (pintype "passive"))
      (node (ref "TP5") (pin "TP") (pinfunction "TP_TP") (pintype "input"))
    )
    (net (code "21") (name "NRF_~{CS}") (class "Default")
      (node (ref "IC1") (pin "21") (pinfunction "PGED2/AN2/C1IND/C2INB/C3IND/RPB0/PMA10/RB0_21") (pintype "bidirectional"))
      (node (ref "IC7") (pin "2") (pinfunction "CSN_2") (pintype "bidirectional"))
      (node (ref "TP6") (pin "TP") (pinfunction "TP_TP") (pintype "input"))
    )
    (net (code "22") (name "Net-(ANT1-FEED)") (class "Default")
      (node (ref "ANT1") (pin "P$1") (pinfunction "FEED_P$1") (pintype "bidirectional"))
      (node (ref "C22") (pin "1") (pinfunction "1_1") (pintype "passive"))
      (node (ref "R21") (pin "2") (pinfunction "2_2") (pintype "passive"))
    )
    (net (code "23") (name "Net-(ANT1-GND)") (class "Default")
      (node (ref "ANT1") (pin "P$2") (pinfunction "GND_P$2") (pintype "bidirectional"))
      (node (ref "C23") (pin "1") (pinfunction "1_1") (pintype "passive"))
    )
    (net (code "24") (name "Net-(C6-Pad1)") (class "Default")
      (node (ref "C6") (pin "1") (pinfunction "1_1") (pintype "passive"))
      (node (ref "R3") (pin "2") (pinfunction "2_2") (pintype "passive"))
      (node (ref "R4") (pin "1") (pinfunction "1_1") (pintype "passive"))
      (node (ref "X1") (pin "1") (pinfunction "1_1") (pintype "passive"))
    )
    (net (code "25") (name "Net-(IC1-OSC1{slash}CLKI{slash}RPA2{slash}RA2)") (class "Default")
      (node (ref "IC1") (pin "30") (pinfunction "OSC1/CLKI/RPA2/RA2_30") (pintype "bidirectional"))
      (node (ref "IC3") (pin "3") (pinfunction "3_3") (pintype "bidirectional"))
    )
    (net (code "26") (name "Net-(IC1-OSC2{slash}CLKO{slash}RPA3{slash}RA3)") (class "Default")
      (node (ref "IC1") (pin "31") (pinfunction "OSC2/CLKO/RPA3/RA3_31") (pintype "bidirectional"))
      (node (ref "IC3") (pin "1") (pinfunction "1_1") (pintype "bidirectional"))
    )
    (net (code "27") (name "Net-(IC1-VCAP)") (class "Default")
      (node (ref "C3") (pin "1") (pinfunction "1_1") (pintype "passive"))
      (node (ref "IC1") (pin "7") (pinfunction "VCAP_7") (pintype "bidirectional"))
    )
    (net (code "28") (name "Net-(IC4-PIO0{slash}KEY)") (class "Default")
      (node (ref "IC4") (pin "PIO0") (pinfunction "PIO0/KEY_PIO0") (pintype "bidirectional"))
      (node (ref "TP12") (pin "TP") (pinfunction "TP_TP") (pintype "input"))
    )
    (net (code "29") (name "Net-(IC4-PIO1{slash}LED)") (class "Default")
      (node (ref "IC4") (pin "PIO1") (pinfunction "PIO1/LED_PIO1") (pintype "bidirectional"))
      (node (ref "R10") (pin "1") (pinfunction "1_1") (pintype "passive"))
    )
    (net (code "30") (name "Net-(IC4-~{RESET})") (class "Default")
      (node (ref "IC4") (pin "RESETB") (pinfunction "~{RESET}_RESETB") (pintype "bidirectional"))
      (node (ref "R9") (pin "2") (pinfunction "2_2") (pintype "passive"))
      (node (ref "TP11") (pin "TP") (pinfunction "TP_TP") (pintype "input"))
    )
    (net (code "31") (name "Net-(IC5-BIN)") (class "Default")
      (node (ref "IC5") (pin "10") (pinfunction "BIN_10") (pintype "bidirectional"))
      (node (ref "R12") (pin "2") (pinfunction "2_2") (pintype "passive"))
    )
    (net (code "32") (name "Net-(IC6-ILIM)") (class "Default")
      (node (ref "IC6") (pin "12") (pinfunction "ILIM_12") (pintype "bidirectional"))
      (node (ref "R17") (pin "2") (pinfunction "2_2") (pintype "passive"))
    )
    (net (code "33") (name "Net-(IC6-ISET)") (class "Default")
      (node (ref "IC6") (pin "16") (pinfunction "ISET_16") (pintype "bidirectional"))
      (node (ref "R18") (pin "2") (pinfunction "2_2") (pintype "passive"))
    )
    (net (code "34") (name "Net-(IC6-TS)") (class "Default")
      (node (ref "IC6") (pin "1") (pinfunction "TS_1") (pintype "bidirectional"))
      (node (ref "R14") (pin "2") (pinfunction "2_2") (pintype "passive"))
    )
    (net (code "35") (name "Net-(IC6-~{CHG})") (class "Default")
      (node (ref "IC6") (pin "9") (pinfunction "~{CHG}_9") (pintype "bidirectional"))
      (node (ref "LED4") (pin "K") (pinfunction "C_K") (pintype "passive"))
      (node (ref "TP17") (pin "TP") (pinfunction "TP_TP") (pintype "input"))
    )
    (net (code "36") (name "Net-(IC7-ANT1)") (class "Default")
      (node (ref "IC7") (pin "12") (pinfunction "ANT1_12") (pintype "bidirectional"))
      (node (ref "L1") (pin "2") (pinfunction "P$2_2") (pintype "bidirectional"))
      (node (ref "L2") (pin "1") (pinfunction "P$1_1") (pintype "bidirectional"))
    )
    (net (code "37") (name "Net-(IC7-ANT2)") (class "Default")
      (node (ref "C18") (pin "1") (pinfunction "1_1") (pintype "passive"))
      (node (ref "IC7") (pin "13") (pinfunction "ANT2_13") (pintype "bidirectional"))
      (node (ref "L1") (pin "1") (pinfunction "P$1_1") (pintype "bidirectional"))
    )
    (net (code "38") (name "Net-(IC7-DVDD)") (class "Default")
      (node (ref "C16") (pin "1") (pinfunction "1_1") (pintype "passive"))
      (node (ref "IC7") (pin "19") (pinfunction "DVDD_19") (pintype "bidirectional"))
    )
    (net (code "39") (name "Net-(IC7-IREF)") (class "Default")
      (node (ref "IC7") (pin "16") (pinfunction "IREF_16") (pintype "bidirectional"))
      (node (ref "R19") (pin "1") (pinfunction "1_1") (pintype "passive"))
    )
    (net (code "40") (name "Net-(IC7-VDD_PA)") (class "Default")
      (node (ref "C17") (pin "1") (pinfunction "1_1") (pintype "passive"))
      (node (ref "C19") (pin "1") (pinfunction "1_1") (pintype "passive"))
      (node (ref "IC7") (pin "11") (pinfunction "VDD_PA_11") (pintype "bidirectional"))
      (node (ref "L2") (pin "2") (pinfunction "P$2_2") (pintype "bidirectional"))
    )
    (net (code "41") (name "Net-(IC7-XC1)") (class "Default")
      (node (ref "IC7") (pin "10") (pinfunction "XC1_10") (pintype "bidirectional"))
      (node (ref "IC8") (pin "3") (pinfunction "3_3") (pintype "bidirectional"))
    )
    (net (code "42") (name "Net-(IC7-XC2)") (class "Default")
      (node (ref "IC7") (pin "9") (pinfunction "XC2_9") (pintype "bidirectional"))
      (node (ref "IC8") (pin "1") (pinfunction "1_1") (pintype "bidirectional"))
    )
    (net (code "43") (name "Net-(IC10-IN)") (class "Default")
      (node (ref "IC10") (pin "1") (pinfunction "IN_1") (pintype "input"))
      (node (ref "S1") (pin "2") (pinfunction "NO_2") (pintype "bidirectional"))
    )
    (net (code "44") (name "Net-(IC10-OUT)") (class "Default")
      (node (ref "IC10") (pin "5") (pinfunction "OUT_5") (pintype "output"))
      (node (ref "IC13") (pin "1") (pinfunction "A_1") (pintype "bidirectional"))
      (node (ref "TP21") (pin "TP") (pinfunction "TP_TP") (pintype "input"))
    )
    (net (code "45") (name "Net-(IC11-L1)") (class "Default")
      (node (ref "IC11") (pin "4") (pinfunction "L1_4") (pintype "bidirectional"))
      (node (ref "L4") (pin "1") (pinfunction "1_1") (pintype "bidirectional"))
    )
    (net (code "46") (name "Net-(IC11-L2)") (class "Default")
      (node (ref "IC11") (pin "2") (pinfunction "L2_2") (pintype "bidirectional"))
      (node (ref "L4") (pin "2") (pinfunction "2_2") (pintype "bidirectional"))
    )
    (net (code "47") (name "Net-(IC11-PS{slash}SYNC)") (class "Default")
      (node (ref "C27") (pin "1") (pinfunction "1_1") (pintype "passive"))
      (node (ref "IC11") (pin "7") (pinfunction "PS/SYNC_7") (pintype "bidirectional"))
      (node (ref "IC11") (pin "8") (pinfunction "VINA_8") (pintype "input"))
      (node (ref "R23") (pin "1") (pinfunction "1_1") (pintype "passive"))
    )
    (net (code "48") (name "Net-(IC12-L1)") (class "Default")
      (node (ref "IC12") (pin "4") (pinfunction "L1_4") (pintype "bidirectional"))
      (node (ref "L5") (pin "1") (pinfunction "1_1") (pintype "bidirectional"))
    )
    (net (code "49") (name "Net-(IC12-L2)") (class "Default")
      (node (ref "IC12") (pin "2") (pinfunction "L2_2") (pintype "bidirectional"))
      (node (ref "L5") (pin "2") (pinfunction "2_2") (pintype "bidirectional"))
    )
    (net (code "50") (name "Net-(IC12-PS{slash}SYNC)") (class "Default")
      (node (ref "C28") (pin "1") (pinfunction "1_1") (pintype "passive"))
      (node (ref "IC12") (pin "7") (pinfunction "PS/SYNC_7") (pintype "bidirectional"))
      (node (ref "IC12") (pin "8") (pinfunction "VINA_8") (pintype "input"))
      (node (ref "R24") (pin "1") (pinfunction "1_1") (pintype "passive"))
    )
    (net (code "51") (name "Net-(J3-SIG)") (class "Default")
      (node (ref "J3") (pin "1") (pinfunction "SIG_1") (pintype "bidirectional"))
      (node (ref "R22") (pin "2") (pinfunction "2_2") (pintype "passive"))
    )
    (net (code "52") (name "Net-(J4-Pad2)") (class "Default")
      (node (ref "J4") (pin "2") (pinfunction "2_2") (pintype "bidirectional"))
      (node (ref "R25") (pin "1") (pinfunction "1_1") (pintype "passive"))
    )
    (net (code "53") (name "Net-(J5-Pad1)") (class "Default")
      (node (ref "J5") (pin "1") (pinfunction "1_1") (pintype "bidirectional"))
      (node (ref "Q2") (pin "C") (pinfunction "C_C") (pintype "passive"))
      (node (ref "R30") (pin "1") (pinfunction "1_1") (pintype "passive"))
    )
    (net (code "54") (name "Net-(J6-Pad2)") (class "Default")
      (node (ref "J6") (pin "2") (pinfunction "2_2") (pintype "bidirectional"))
      (node (ref "R32") (pin "1") (pinfunction "1_1") (pintype "passive"))
    )
    (net (code "55") (name "Net-(J7-Pad1)") (class "Default")
      (node (ref "J7") (pin "1") (pinfunction "1_1") (pintype "bidirectional"))
      (node (ref "Q3") (pin "C") (pinfunction "C_C") (pintype "passive"))
      (node (ref "R36") (pin "1") (pinfunction "1_1") (pintype "passive"))
    )
    (net (code "56") (name "Net-(L3-P$1)") (class "Default")
      (node (ref "C18") (pin "2") (pinfunction "2_2") (pintype "passive"))
      (node (ref "C20") (pin "1") (pinfunction "1_1") (pintype "passive"))
      (node (ref "L3") (pin "1") (pinfunction "P$1_1") (pintype "bidirectional"))
    )
    (net (code "57") (name "Net-(L3-P$2)") (class "Default")
      (node (ref "C21") (pin "1") (pinfunction "1_1") (pintype "passive"))
      (node (ref "L3") (pin "2") (pinfunction "P$2_2") (pintype "bidirectional"))
      (node (ref "R21") (pin "1") (pinfunction "1_1") (pintype "passive"))
      (node (ref "R22") (pin "1") (pinfunction "1_1") (pintype "passive"))
    )
    (net (code "58") (name "Net-(LED1-C)") (class "Default")
      (node (ref "LED1") (pin "K") (pinfunction "C_K") (pintype "passive"))
      (node (ref "R1") (pin "1") (pinfunction "1_1") (pintype "passive"))
    )
    (net (code "59") (name "Net-(LED2-PadC)") (class "Default")
      (node (ref "LED2") (pin "C") (pinfunction "C_C") (pintype "passive"))
      (node (ref "R2") (pin "1") (pinfunction "1_1") (pintype "passive"))
    )
    (net (code "60") (name "Net-(LED3-PadA)") (class "Default")
      (node (ref "LED3") (pin "A") (pinfunction "A_A") (pintype "passive"))
      (node (ref "R10") (pin "2") (pinfunction "2_2") (pintype "passive"))
    )
    (net (code "61") (name "Net-(LED4-PadA)") (class "Default")
      (node (ref "LED4") (pin "A") (pinfunction "A_A") (pintype "passive"))
      (node (ref "R16") (pin "2") (pinfunction "2_2") (pintype "passive"))
    )
    (net (code "62") (name "Net-(LED5-PadC)") (class "Default")
      (node (ref "LED5") (pin "C") (pinfunction "C_C") (pintype "passive"))
      (node (ref "R30") (pin "2") (pinfunction "2_2") (pintype "passive"))
    )
    (net (code "63") (name "Net-(LED6-PadC)") (class "Default")
      (node (ref "LED6") (pin "C") (pinfunction "C_C") (pintype "passive"))
      (node (ref "R36") (pin "2") (pinfunction "2_2") (pintype "passive"))
    )
    (net (code "64") (name "Net-(Q1-PadB)") (class "Default")
      (node (ref "Q1") (pin "B") (pinfunction "B_B") (pintype "passive"))
      (node (ref "R25") (pin "2") (pinfunction "2_2") (pintype "passive"))
      (node (ref "R27") (pin "1") (pinfunction "1_1") (pintype "passive"))
    )
    (net (code "65") (name "Net-(Q2-PadB)") (class "Default")
      (node (ref "Q2") (pin "B") (pinfunction "B_B") (pintype "passive"))
      (node (ref "R26") (pin "2") (pinfunction "2_2") (pintype "passive"))
      (node (ref "R29") (pin "1") (pinfunction "1_1") (pintype "passive"))
      (node (ref "TP25") (pin "TP") (pinfunction "TP_TP") (pintype "input"))
    )
    (net (code "66") (name "Net-(Q3-PadB)") (class "Default")
      (node (ref "Q3") (pin "B") (pinfunction "B_B") (pintype "passive"))
      (node (ref "R31") (pin "2") (pinfunction "2_2") (pintype "passive"))
      (node (ref "R33") (pin "1") (pinfunction "1_1") (pintype "passive"))
      (node (ref "TP26") (pin "TP") (pinfunction "TP_TP") (pintype "input"))
    )
    (net (code "67") (name "Net-(Q4-PadB)") (class "Default")
      (node (ref "Q4") (pin "B") (pinfunction "B_B") (pintype "passive"))
      (node (ref "R32") (pin "2") (pinfunction "2_2") (pintype "passive"))
      (node (ref "R34") (pin "1") (pinfunction "1_1") (pintype "passive"))
    )
    (net (code "68") (name "Net-(U1-Y)") (class "Default")
      (node (ref "R26") (pin "1") (pinfunction "1_1") (pintype "passive"))
      (node (ref "U1") (pin "4") (pinfunction "Y_4") (pintype "bidirectional"))
    )
    (net (code "69") (name "Net-(U2-Y)") (class "Default")
      (node (ref "R31") (pin "1") (pinfunction "1_1") (pintype "passive"))
      (node (ref "U2") (pin "4") (pinfunction "Y_4") (pintype "bidirectional"))
    )
    (net (code "70") (name "PGEC") (class "Default")
      (node (ref "IC1") (pin "13") (pinfunction "PGEC4/TCK/CTED8/PMD3/RA7_13") (pintype "bidirectional"))
      (node (ref "SV1") (pin "5") (pinfunction "5_5") (pintype "passive"))
    )
    (net (code "71") (name "PGED") (class "Default")
      (node (ref "IC1") (pin "12") (pinfunction "PGED4/PMD0/RA10_12") (pintype "bidirectional"))
      (node (ref "SV1") (pin "4") (pinfunction "4_4") (pintype "passive"))
    )
    (net (code "72") (name "SPI1_SCK") (class "Default")
      (node (ref "IC1") (pin "14") (pinfunction "CVREFOUT/AN10/C3INB/RPB14/SCK1/CTED5/RB14_14") (pintype "bidirectional"))
      (node (ref "IC7") (pin "3") (pinfunction "SCK_3") (pintype "bidirectional"))
      (node (ref "TP7") (pin "TP") (pinfunction "TP_TP") (pintype "input"))
    )
    (net (code "73") (name "SPI1_SDI") (class "Default")
      (node (ref "IC1") (pin "22") (pinfunction "PGEC2/AN3/C1INC/C2INA/LVDIN/RPB1/CTED12/PMA9/RB1_22") (pintype "bidirectional"))
      (node (ref "IC7") (pin "5") (pinfunction "MISO_5") (pintype "bidirectional"))
      (node (ref "TP4") (pin "TP") (pinfunction "TP_TP") (pintype "input"))
    )
    (net (code "74") (name "SPI1_SDO") (class "Default")
      (node (ref "IC1") (pin "20") (pinfunction "PGEC3/VREF-/AN1/RPA1/ASCL1/CTED2/PMA6/RA1_20") (pintype "bidirectional"))
      (node (ref "IC7") (pin "4") (pinfunction "MOSI_4") (pintype "bidirectional"))
      (node (ref "TP3") (pin "TP") (pinfunction "TP_TP") (pintype "input"))
    )
    (net (code "75") (name "STS_L") (class "Default")
      (node (ref "IC1") (pin "44") (pinfunction "RPB8/SCL1/CTED10/PMA4/RB8_44") (pintype "bidirectional"))
      (node (ref "J6") (pin "3") (pinfunction "3_3") (pintype "bidirectional"))
    )
    (net (code "76") (name "STS_R") (class "Default")
      (node (ref "IC1") (pin "25") (pinfunction "AN6/RPC0/RC0_25") (pintype "bidirectional"))
      (node (ref "J4") (pin "3") (pinfunction "3_3") (pintype "bidirectional"))
    )
    (net (code "77") (name "SYS_EN") (class "Default")
      (node (ref "IC11") (pin "6") (pinfunction "EN_6") (pintype "bidirectional"))
      (node (ref "IC12") (pin "6") (pinfunction "EN_6") (pintype "bidirectional"))
      (node (ref "IC13") (pin "4") (pinfunction "Y_4") (pintype "bidirectional"))
      (node (ref "TP24") (pin "TP") (pinfunction "TP_TP") (pintype "input"))
    )
    (net (code "78") (name "U1_RX") (class "Default")
      (node (ref "IC1") (pin "36") (pinfunction "AN12/RPC3/RC3_36") (pintype "bidirectional"))
      (node (ref "IC4") (pin "UART_TX") (pinfunction "UART_TX_UART_TX") (pintype "bidirectional"))
      (node (ref "TP9") (pin "TP") (pinfunction "TP_TP") (pintype "input"))
    )
    (net (code "79") (name "U1_TX") (class "Default")
      (node (ref "IC1") (pin "43") (pinfunction "RPB7/CTED3/PMA5/INT0/RB7_43") (pintype "bidirectional"))
      (node (ref "IC4") (pin "UART_RX") (pinfunction "UART_RX_UART_RX") (pintype "bidirectional"))
      (node (ref "TP10") (pin "TP") (pinfunction "TP_TP") (pintype "input"))
    )
    (net (code "80") (name "U2_RX") (class "Default")
      (node (ref "IC1") (pin "4") (pinfunction "RPC8/PMD5/RC8_4") (pintype "bidirectional"))
      (node (ref "JP1") (pin "2") (pinfunction "2_2") (pintype "passive"))
    )
    (net (code "81") (name "U2_TX") (class "Default")
      (node (ref "IC1") (pin "5") (pinfunction "RPC9/CTED7/PMD6/RC9_5") (pintype "bidirectional"))
      (node (ref "JP1") (pin "1") (pinfunction "1_1") (pintype "passive"))
    )
    (net (code "82") (name "USB_D+") (class "Default")
      (node (ref "IC1") (pin "8") (pinfunction "D+_8") (pintype "bidirectional"))
      (node (ref "IC2") (pin "1") (pinfunction "A_1") (pintype "input"))
      (node (ref "IC2") (pin "6") (pinfunction "A_6") (pintype "input"))
      (node (ref "J1") (pin "3") (pinfunction "D+_3") (pintype "bidirectional"))
    )
    (net (code "83") (name "USB_D-") (class "Default")
      (node (ref "IC1") (pin "9") (pinfunction "D-_9") (pintype "bidirectional"))
      (node (ref "IC2") (pin "3") (pinfunction "B_3") (pintype "input"))
      (node (ref "IC2") (pin "4") (pinfunction "B_4") (pintype "input"))
      (node (ref "J1") (pin "2") (pinfunction "D-_2") (pintype "bidirectional"))
    )
    (net (code "84") (name "USB_ID") (class "Default")
      (node (ref "IC1") (pin "41") (pinfunction "TMS/RPB5/USBID/RB5_41") (pintype "bidirectional"))
      (node (ref "J1") (pin "4") (pinfunction "ID_4") (pintype "bidirectional"))
    )
    (net (code "85") (name "VBAT") (class "Default")
      (node (ref "C10") (pin "1") (pinfunction "1_1") (pintype "passive"))
      (node (ref "IC5") (pin "7") (pinfunction "SRN_7") (pintype "bidirectional"))
      (node (ref "IC6") (pin "2") (pinfunction "BAT_1_2") (pintype "bidirectional"))
      (node (ref "IC6") (pin "3") (pinfunction "BAT_2_3") (pintype "bidirectional"))
      (node (ref "R11") (pin "2") (pinfunction "2_2") (pintype "passive"))
      (node (ref "TP14") (pin "TP") (pinfunction "TP_TP") (pintype "input"))
    )
    (net (code "86") (name "VCCINT") (class "Default")
      (node (ref "C12") (pin "1") (pinfunction "1_1") (pintype "passive"))
      (node (ref "C25") (pin "1") (pinfunction "1_1") (pintype "passive"))
      (node (ref "C26") (pin "1") (pinfunction "1_1") (pintype "passive"))
      (node (ref "IC10") (pin "6") (pinfunction "VCC_6") (pintype "power_in"))
      (node (ref "IC11") (pin "5") (pinfunction "VIN_5") (pintype "input"))
      (node (ref "IC12") (pin "5") (pinfunction "VIN_5") (pintype "input"))
      (node (ref "IC13") (pin "5") (pinfunction "VCC_5") (pintype "bidirectional"))
      (node (ref "IC6") (pin "10") (pinfunction "OUT_1_10") (pintype "output"))
      (node (ref "IC6") (pin "11") (pinfunction "OUT_2_11") (pintype "output"))
      (node (ref "R16") (pin "1") (pinfunction "1_1") (pintype "passive"))
      (node (ref "R23") (pin "2") (pinfunction "2_2") (pintype "passive"))
      (node (ref "R24") (pin "2") (pinfunction "2_2") (pintype "passive"))
      (node (ref "TP19") (pin "TP") (pinfunction "TP_TP") (pintype "input"))
    )
    (net (code "87") (name "VDD") (class "Default")
      (node (ref "C11") (pin "1") (pinfunction "1_1") (pintype "passive"))
      (node (ref "IC1") (pin "42") (pinfunction "VBUS_42") (pintype "bidirectional"))
      (node (ref "IC6") (pin "13") (pinfunction "IN_13") (pintype "input"))
      (node (ref "J1") (pin "1") (pinfunction "VDD_1") (pintype "bidirectional"))
      (node (ref "TP15") (pin "TP") (pinfunction "TP_TP") (pintype "input"))
    )
    (net (code "88") (name "_VBAT") (class "Default")
      (node (ref "C8") (pin "1") (pinfunction "1_1") (pintype "passive"))
      (node (ref "IC5") (pin "6") (pinfunction "BAT_6") (pintype "bidirectional"))
      (node (ref "IC5") (pin "8") (pinfunction "SRP_8") (pintype "bidirectional"))
      (node (ref "J2") (pin "2") (pinfunction "2_2") (pintype "bidirectional"))
      (node (ref "R11") (pin "1") (pinfunction "1_1") (pintype "passive"))
      (node (ref "TP13") (pin "TP") (pinfunction "TP_TP") (pintype "input"))
    )
    (net (code "89") (name "unconnected-(IC4-PadPIO2)") (class "Default")
      (node (ref "IC4") (pin "PIO2") (pinfunction "PIO2_PIO2") (pintype "bidirectional"))
    )
    (net (code "90") (name "unconnected-(IC4-PadPIO3)") (class "Default")
      (node (ref "IC4") (pin "PIO3") (pinfunction "PIO3_PIO3") (pintype "bidirectional"))
    )
    (net (code "91") (name "unconnected-(IC4-PadUART_CTS)") (class "Default")
      (node (ref "IC4") (pin "UART_CTS") (pinfunction "UART_CTS_UART_CTS") (pintype "bidirectional"))
    )
    (net (code "92") (name "unconnected-(IC4-PadUART_RTS)") (class "Default")
      (node (ref "IC4") (pin "UART_RTS") (pinfunction "UART_RTS_UART_RTS") (pintype "bidirectional"))
    )
    (net (code "93") (name "unconnected-(IC6-TMR-Pad14)") (class "Default")
      (node (ref "IC6") (pin "14") (pinfunction "TMR_14") (pintype "bidirectional"))
    )
    (net (code "94") (name "unconnected-(IC10-~{OUT}-Pad4)") (class "Default")
      (node (ref "IC10") (pin "4") (pinfunction "~{OUT}_4") (pintype "output"))
    )
    (net (code "95") (name "unconnected-(S1-Pad3)") (class "Default")
      (node (ref "S1") (pin "3") (pinfunction "3_3") (pintype "bidirectional"))
    )
    (net (code "96") (name "unconnected-(S1-Pad4)") (class "Default")
      (node (ref "S1") (pin "4") (pinfunction "4_4") (pintype "bidirectional"))
    )
    (net (code "97") (name "unconnected-(SV1-Pad6)") (class "Default")
      (node (ref "SV1") (pin "6") (pinfunction "6_6") (pintype "passive"))
    )
    (net (code "98") (name "~{MCLR}") (class "Default")
      (node (ref "IC1") (pin "18") (pinfunction "~{MCLR}_18") (pintype "bidirectional"))
      (node (ref "R3") (pin "1") (pinfunction "1_1") (pintype "passive"))
      (node (ref "SV1") (pin "1") (pinfunction "1_1") (pintype "passive"))
    )
  )
)
